# OBCv4_21.net
KiCad netlist of a schematic drawn in EAGLE
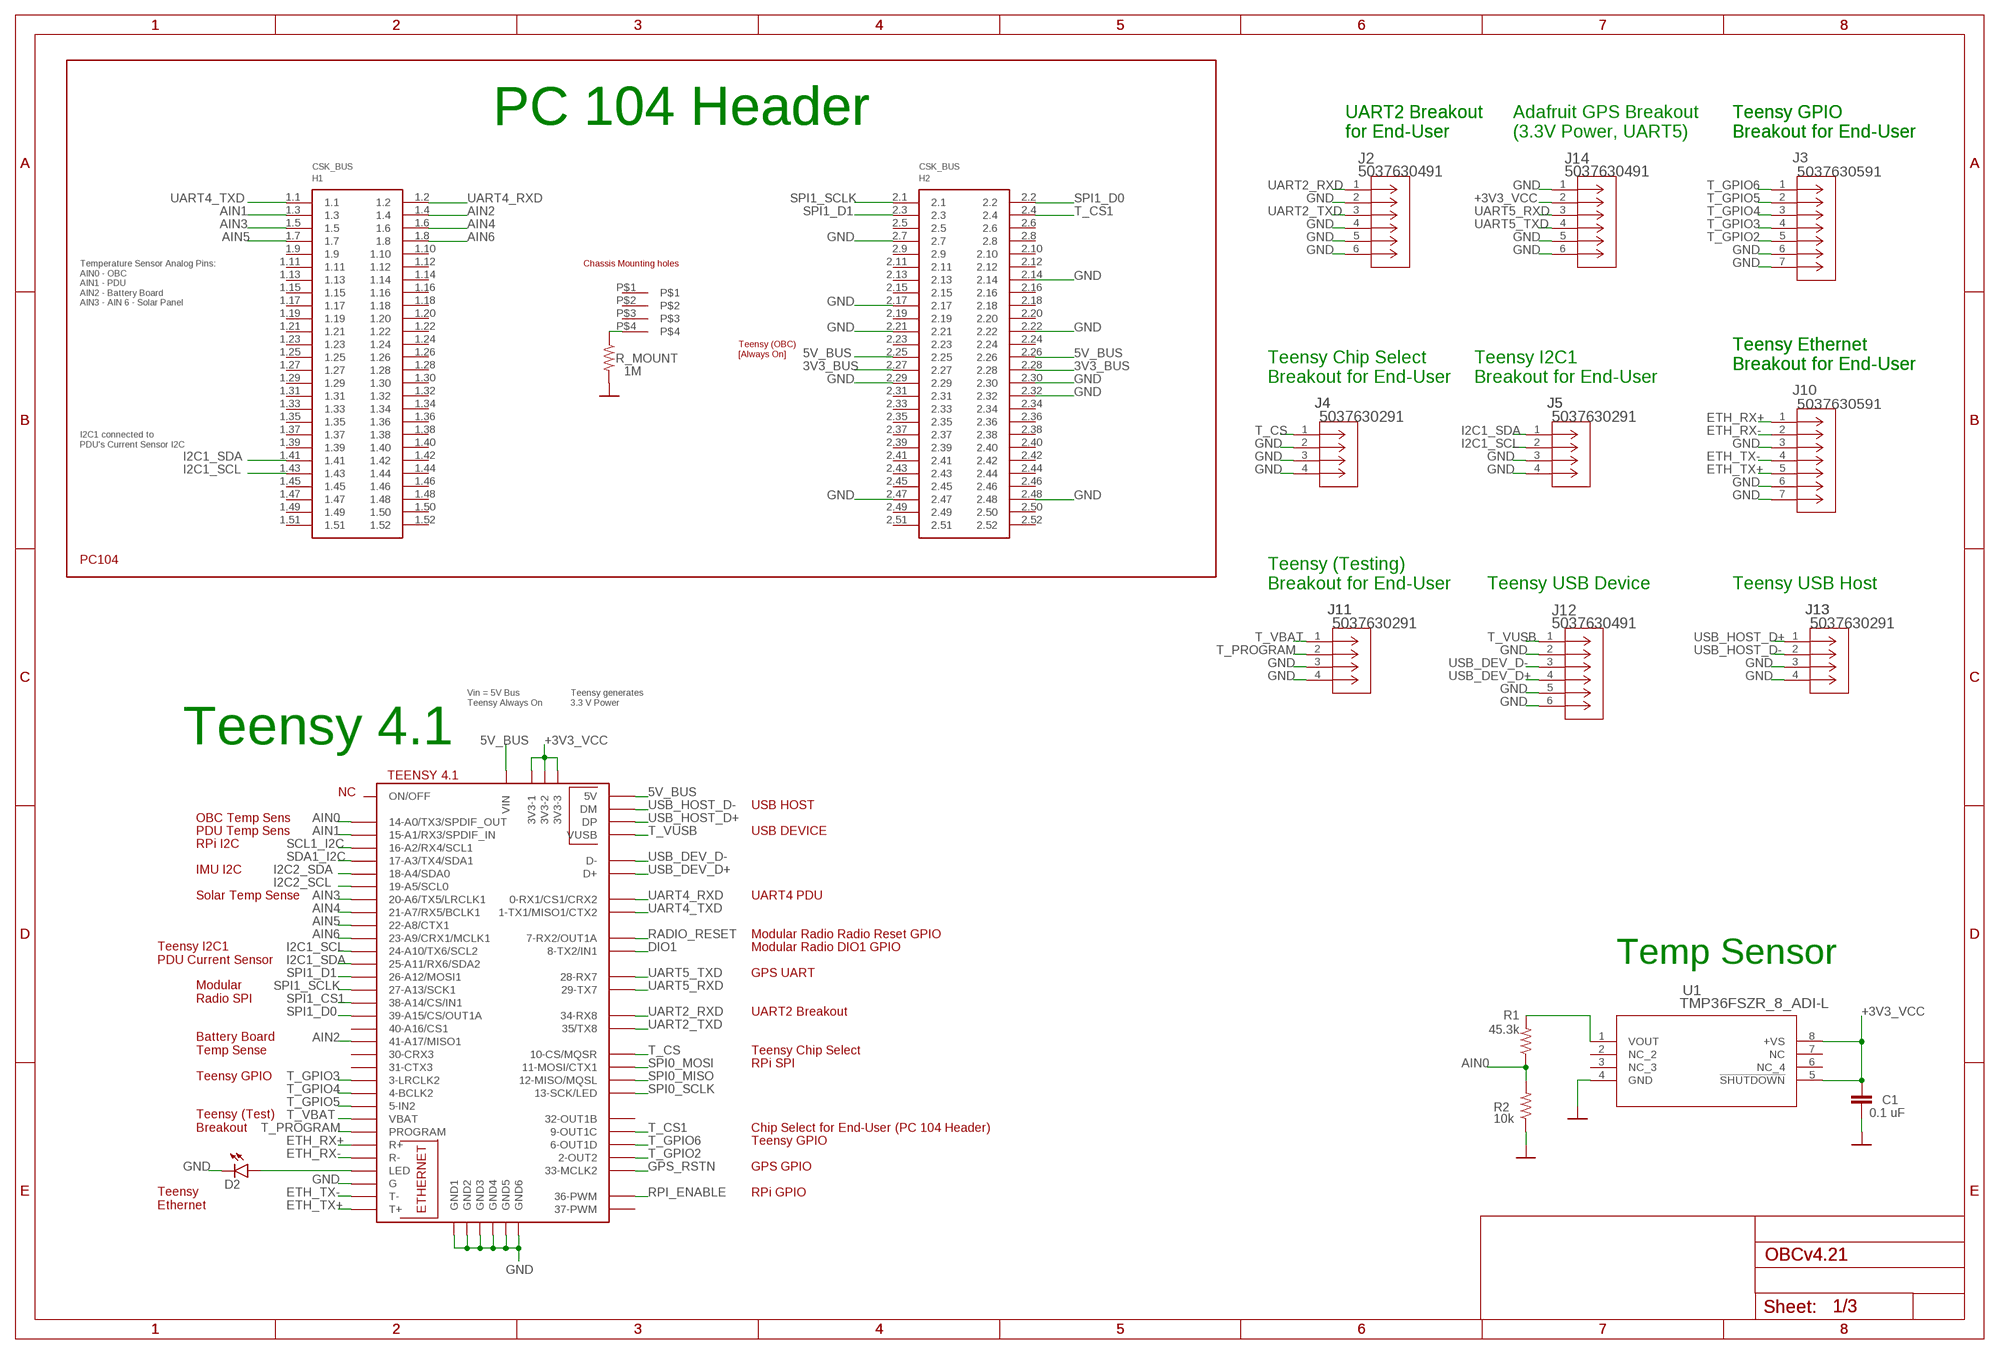
[diagram p0: schematic, sheet 1]
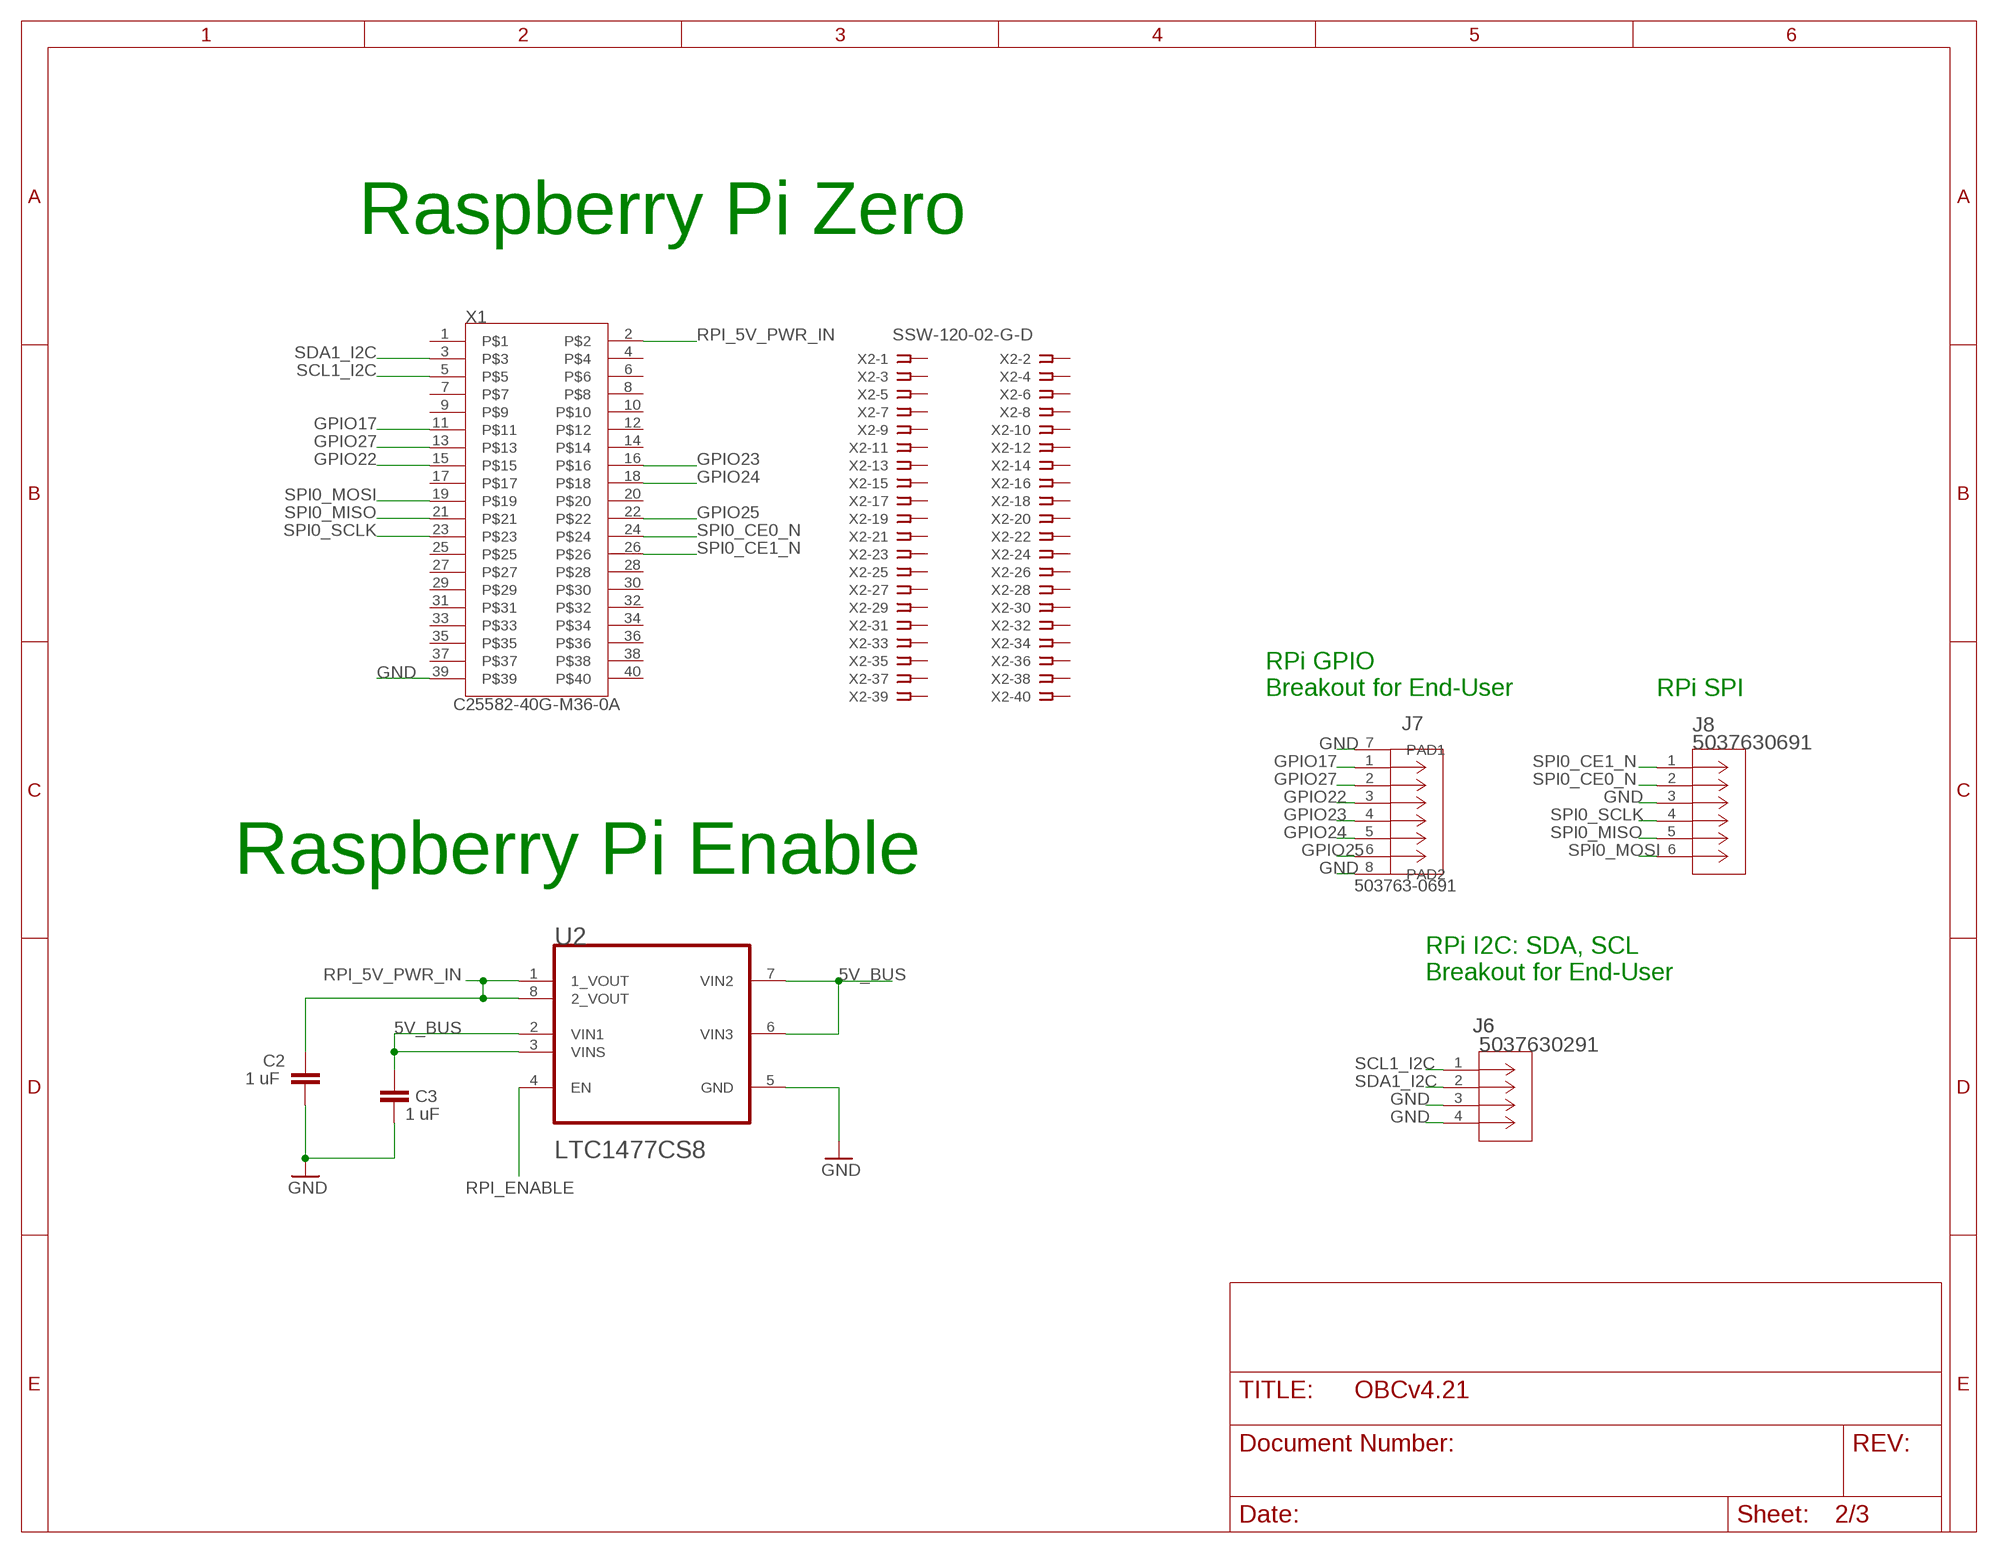
[diagram p1: schematic, sheet 2]
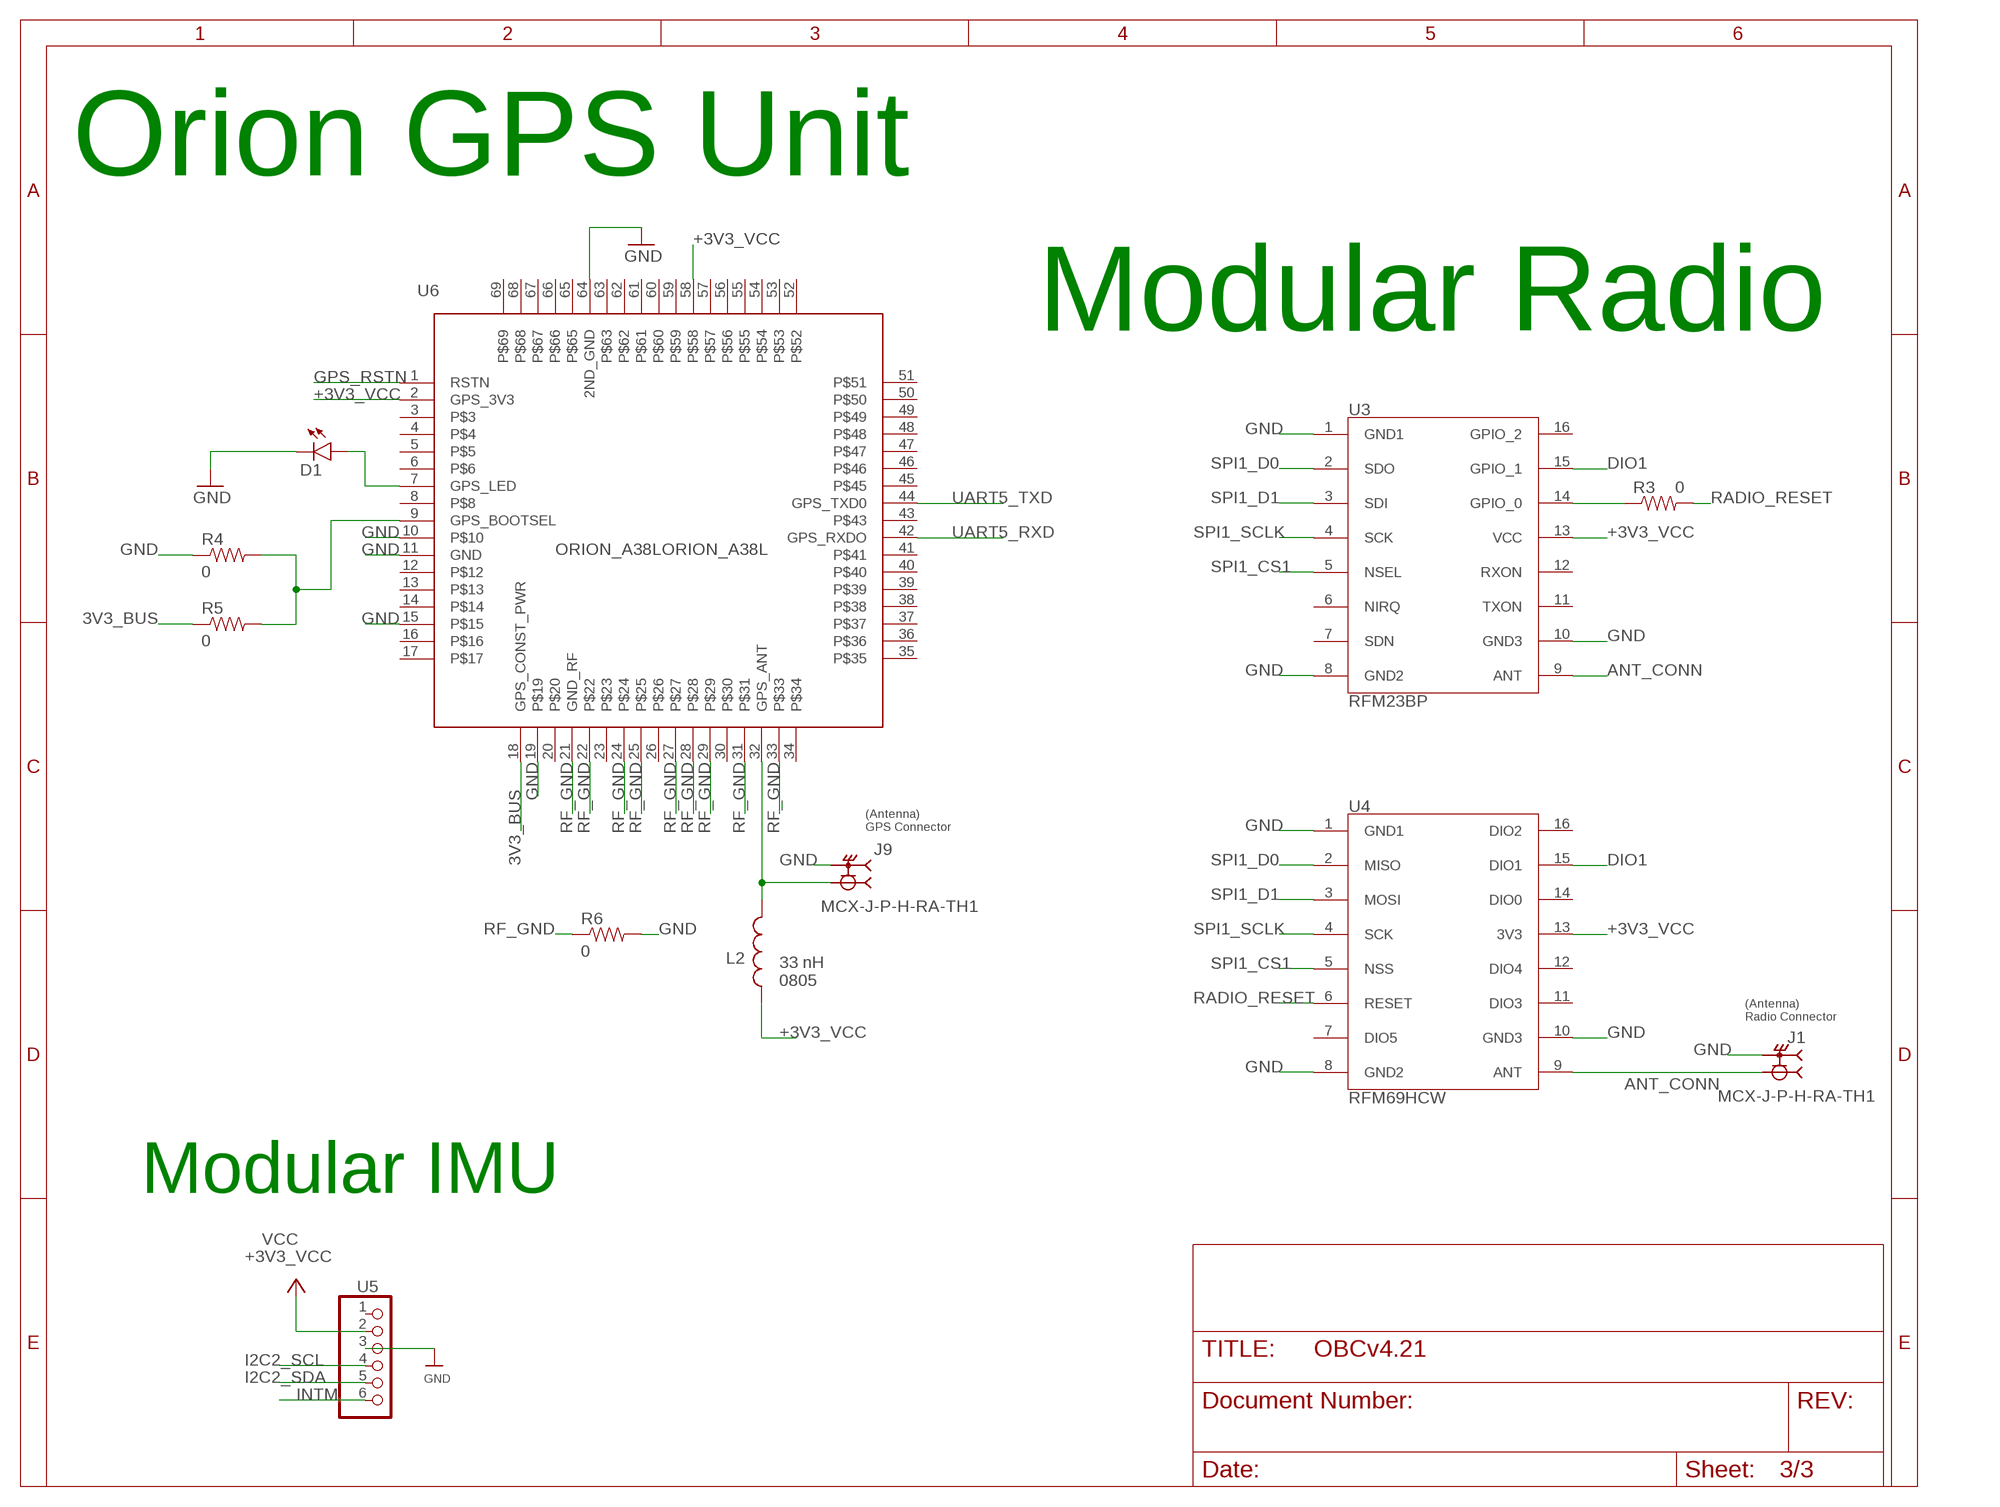
[diagram p2: schematic, sheet 3]

(export (version "E")
  (design (tool "Eeschema 10.0.6"))
  (components
    (comp (ref "D1")
      (value "LEDCHIP-LED0603")
      (footprint "eagle-import:CHIP-LED0603")
      (libsource (lib "eagle-import") (part "LEDCHIP-LED0603"))
    )
    (comp (ref "J1")
      (value "MCX-J-P-H-RA-TH1")
      (footprint "eagle-import:SAMTEC_MCX-J-P-H-RA-TH1")
      (fields (field (name "DIGI-KEY_PART_NUMBER") "SAM10607-ND") (field (name "MF") "Samtec"))
      (libsource (lib "eagle-import") (part "MCX-J-P-H-RA-TH1"))
    )
    (comp (ref "J9")
      (value "MCX-J-P-H-RA-TH1")
      (footprint "eagle-import:SAMTEC_MCX-J-P-H-RA-TH1")
      (fields (field (name "DIGI-KEY_PART_NUMBER") "SAM10607-ND") (field (name "MF") "Samtec"))
      (libsource (lib "eagle-import") (part "MCX-J-P-H-RA-TH1"))
    )
    (comp (ref "L2")
      (value "AIMC-0805-2N2S-T")
      (footprint "eagle-import:INDC2012X105N")
      (fields (field (name "DIGI-KEY_PART_NUMBER") "535-11562-1-ND") (field (name "MF") "Abracon"))
      (libsource (lib "eagle-import") (part "AIMC-0805-2N2S-T"))
    )
    (comp (ref "R3")
      (value "0")
      (footprint "eagle-import:0805")
      (libsource (lib "eagle-import") (part "RESISTOR0805-RES"))
    )
    (comp (ref "R4")
      (value "0")
      (footprint "eagle-import:0805")
      (libsource (lib "eagle-import") (part "RESISTOR0805-RES"))
    )
    (comp (ref "R5")
      (value "0")
      (footprint "eagle-import:0805")
      (libsource (lib "eagle-import") (part "RESISTOR0805-RES"))
    )
    (comp (ref "R6")
      (value "0")
      (footprint "eagle-import:0805")
      (libsource (lib "eagle-import") (part "RESISTOR0805-RES"))
    )
    (comp (ref "U3")
      (value "RFM23BP")
      (footprint "eagle-import:RFM23BP")
      (libsource (lib "eagle-import") (part "RFM23BP"))
    )
    (comp (ref "U4")
      (value "RFM69HCW")
      (footprint "eagle-import:RFM69HCW")
      (libsource (lib "eagle-import") (part "RFM69HCW"))
    )
    (comp (ref "U5")
      (value "HEADER-1X670MIL")
      (footprint "eagle-import:1X06_ROUND_70")
      (libsource (lib "eagle-import") (part "HEADER-1X670MIL"))
    )
    (comp (ref "U6")
      (value "ORION_A38LORION_A38L")
      (footprint "eagle-import:ORION_A38L")
      (libsource (lib "eagle-import") (part "ORION_A38LORION_A38L"))
    )
    (comp (ref "C1")
      (value "0.1 uF")
      (footprint "eagle-import:0805")
      (libsource (lib "eagle-import") (part "CAP0805"))
    )
    (comp (ref "D2")
      (value "LEDCHIP-LED0603")
      (footprint "eagle-import:CHIP-LED0603")
      (libsource (lib "eagle-import") (part "LEDCHIP-LED0603"))
    )
    (comp (ref "H1")
      (value "PC104_WCONN")
      (footprint "eagle-import:PC104_WCONN")
      (libsource (lib "eagle-import") (part "PC104_WCONN"))
    )
    (comp (ref "J2")
      (value "5037630491")
      (footprint "eagle-import:CON_5037630491")
      (fields (field (name "COPYRIGHT") "Copyright (C) 2018 Accelerated Designs. All rights reserved"))
      (libsource (lib "eagle-import") (part "5037630491"))
    )
    (comp (ref "J3")
      (value "5037630591")
      (footprint "eagle-import:CON_5037630591")
      (fields (field (name "COPYRIGHT") "Copyright (C) 2021 Ultra Librarian. All rights reserved."))
      (libsource (lib "eagle-import") (part "5037630591"))
    )
    (comp (ref "J4")
      (value "5037630291")
      (footprint "eagle-import:CON_5037630291")
      (fields (field (name "COPYRIGHT") "Copyright (C) 2018 Accelerated Designs. All rights reserved"))
      (libsource (lib "eagle-import") (part "5037630291"))
    )
    (comp (ref "J5")
      (value "5037630291")
      (footprint "eagle-import:CON_5037630291")
      (fields (field (name "COPYRIGHT") "Copyright (C) 2018 Accelerated Designs. All rights reserved"))
      (libsource (lib "eagle-import") (part "5037630291"))
    )
    (comp (ref "J10")
      (value "5037630591")
      (footprint "eagle-import:CON_5037630591")
      (fields (field (name "COPYRIGHT") "Copyright (C) 2021 Ultra Librarian. All rights reserved."))
      (libsource (lib "eagle-import") (part "5037630591"))
    )
    (comp (ref "J11")
      (value "5037630291")
      (footprint "eagle-import:CON_5037630291")
      (fields (field (name "COPYRIGHT") "Copyright (C) 2018 Accelerated Designs. All rights reserved"))
      (libsource (lib "eagle-import") (part "5037630291"))
    )
    (comp (ref "J12")
      (value "5037630491")
      (footprint "eagle-import:CON_5037630491")
      (fields (field (name "COPYRIGHT") "Copyright (C) 2018 Accelerated Designs. All rights reserved"))
      (libsource (lib "eagle-import") (part "5037630491"))
    )
    (comp (ref "J13")
      (value "5037630291")
      (footprint "eagle-import:CON_5037630291")
      (fields (field (name "COPYRIGHT") "Copyright (C) 2018 Accelerated Designs. All rights reserved"))
      (libsource (lib "eagle-import") (part "5037630291"))
    )
    (comp (ref "J14")
      (value "5037630491")
      (footprint "eagle-import:CON_5037630491")
      (fields (field (name "COPYRIGHT") "Copyright (C) 2018 Accelerated Designs. All rights reserved"))
      (libsource (lib "eagle-import") (part "5037630491"))
    )
    (comp (ref "R1")
      (value "45.3k")
      (footprint "eagle-import:0805")
      (libsource (lib "eagle-import") (part "RESISTOR0805-RES"))
    )
    (comp (ref "R2")
      (value "10k")
      (footprint "eagle-import:0805")
      (libsource (lib "eagle-import") (part "RESISTOR0805-RES"))
    )
    (comp (ref "R_MOUNT")
      (value "1M")
      (footprint "eagle-import:0805")
      (libsource (lib "eagle-import") (part "RESISTOR0805-RES"))
    )
    (comp (ref "U$1")
      (value "TEENSY41")
      (footprint "eagle-import:TEENSY41")
      (libsource (lib "eagle-import") (part "TEENSY41"))
    )
    (comp (ref "U1")
      (value "TMP36FSZR_8_ADI-L")
      (footprint "eagle-import:R_8_ADI-L")
      (fields
        (field (name "MANUFACTURER_PART_NUMBER") "TMP36FSZ")
        (field (name "COPYRIGHT") "Copyright (C) 2021 Ultra Librarian. All rights reserved.")
      )
      (libsource (lib "eagle-import") (part "TMP36FSZR_8_ADI-L"))
    )
    (comp (ref "C2")
      (value "1 uF")
      (footprint "eagle-import:0805")
      (libsource (lib "eagle-import") (part "CAP0805"))
    )
    (comp (ref "C3")
      (value "1 uF")
      (footprint "eagle-import:0805")
      (libsource (lib "eagle-import") (part "CAP0805"))
    )
    (comp (ref "J6")
      (value "5037630291")
      (footprint "eagle-import:CON_5037630291")
      (fields (field (name "COPYRIGHT") "Copyright (C) 2018 Accelerated Designs. All rights reserved"))
      (libsource (lib "eagle-import") (part "5037630291"))
    )
    (comp (ref "J7")
      (value "503763-0691")
      (footprint "eagle-import:CONN_503763-0691_MOL")
      (fields (field (name "COPYRIGHT") "Copyright (C) 2018 Accelerated Designs. All rights reserved"))
      (libsource (lib "eagle-import") (part "503763-0691"))
    )
    (comp (ref "J8")
      (value "5037630691")
      (footprint "eagle-import:CONN_503763-0691_MOL")
      (fields
        (field (name "MANUFACTURER_PART_NUMBER") "503763-0691")
        (field (name "COPYRIGHT") "Copyright (C) 2018 Accelerated Designs. All rights reserved")
      )
      (libsource (lib "eagle-import") (part "5037630691"))
    )
    (comp (ref "U2")
      (value "LTC1477CS8LINEAR_TECHNOLOGY_LTC1477CS8_0_2")
      (footprint "eagle-import:LINEAR_TECHNOLOGY_LTC1477CS8_2")
      (fields (field (name "MF") "Linear Technology") (field (name "MPN") "LTC1477CS8"))
      (libsource (lib "eagle-import") (part "LTC1477CS8LINEAR_TECHNOLOGY_LTC1477CS8_0_2"))
    )
    (comp (ref "X1")
      (value "C25582-40G-M36-0A")
      (footprint "eagle-import:ADAFRUIT_C25582-40G-M36-0A_0")
      (libsource (lib "eagle-import") (part "C25582-40G-M36-0A"))
    )
    (comp (ref "X2")
      (value "SSW-120-02-G-D")
      (footprint "eagle-import:SSW-120-02-G-D")
      (fields (field (name "MF") "Samtec Inc."))
      (libsource (lib "eagle-import") (part "SSW-120-02-G-D"))
    )
  )
  (nets
    (net (code "1") (name "+3V3_VCC") (class "Default")
      (node (ref "C1") (pin "1") (pinfunction "1_1") (pintype "passive"))
      (node (ref "J14") (pin "2") (pinfunction "2_2") (pintype "passive"))
      (node (ref "L2") (pin "1") (pinfunction "1_1") (pintype "passive"))
      (node (ref "U$1") (pin "3V3-1") (pinfunction "3V3-1_3V3-1") (pintype "bidirectional"))
      (node (ref "U$1") (pin "3V3-2") (pinfunction "3V3-2_3V3-2") (pintype "bidirectional"))
      (node (ref "U$1") (pin "3V3-3") (pinfunction "3V3-3_3V3-3") (pintype "bidirectional"))
      (node (ref "U1") (pin "5") (pinfunction "~{SHUTDOWN}_5") (pintype "passive"))
      (node (ref "U1") (pin "8") (pinfunction "+VS_8") (pintype "power_in"))
      (node (ref "U3") (pin "13") (pinfunction "VCC_13") (pintype "bidirectional"))
      (node (ref "U4") (pin "13") (pinfunction "3V3_13") (pintype "bidirectional"))
      (node (ref "U5") (pin "2") (pinfunction "2_2") (pintype "passive"))
      (node (ref "U6") (pin "2") (pinfunction "GPS_3V3_2") (pintype "bidirectional"))
      (node (ref "U6") (pin "58") (pinfunction "P$58_58") (pintype "bidirectional"))
    )
    (net (code "2") (name "3V3_BUS") (class "Default")
      (node (ref "H1") (pin "2.27") (pinfunction "2.27_2.27") (pintype "bidirectional"))
      (node (ref "H1") (pin "2.28") (pinfunction "2.28_2.28") (pintype "bidirectional"))
      (node (ref "R5") (pin "1") (pinfunction "1_1") (pintype "passive"))
      (node (ref "U6") (pin "18") (pinfunction "GPS_CONST_PWR_18") (pintype "bidirectional"))
    )
    (net (code "3") (name "5V_BUS") (class "Default")
      (node (ref "C3") (pin "1") (pinfunction "1_1") (pintype "passive"))
      (node (ref "H1") (pin "2.25") (pinfunction "2.25_2.25") (pintype "bidirectional"))
      (node (ref "H1") (pin "2.26") (pinfunction "2.26_2.26") (pintype "bidirectional"))
      (node (ref "U$1") (pin "+5V") (pinfunction "5V_+5V") (pintype "bidirectional"))
      (node (ref "U$1") (pin "VIN") (pinfunction "VIN_VIN") (pintype "bidirectional"))
      (node (ref "U2") (pin "2") (pinfunction "VIN1_2") (pintype "power_in"))
      (node (ref "U2") (pin "3") (pinfunction "VINS_3") (pintype "power_in"))
      (node (ref "U2") (pin "6") (pinfunction "VIN3_6") (pintype "power_in"))
      (node (ref "U2") (pin "7") (pinfunction "VIN2_7") (pintype "power_in"))
    )
    (net (code "4") (name "AIN0") (class "Default")
      (node (ref "R1") (pin "1") (pinfunction "1_1") (pintype "passive"))
      (node (ref "R2") (pin "2") (pinfunction "2_2") (pintype "passive"))
      (node (ref "U$1") (pin "14-A0/TX3/SPDIF_OUT") (pinfunction "14-A0/TX3/SPDIF_OUT_14-A0/TX3/SPDIF_OUT") (pintype "bidirectional"))
    )
    (net (code "5") (name "AIN1") (class "Default")
      (node (ref "H1") (pin "1.3") (pinfunction "1.3_1.3") (pintype "bidirectional"))
      (node (ref "U$1") (pin "15-A1/RX3/SPDIF_IN") (pinfunction "15-A1/RX3/SPDIF_IN_15-A1/RX3/SPDIF_IN") (pintype "bidirectional"))
    )
    (net (code "6") (name "AIN2") (class "Default")
      (node (ref "H1") (pin "1.4") (pinfunction "1.4_1.4") (pintype "bidirectional"))
      (node (ref "U$1") (pin "41-A17/MISO1") (pinfunction "41-A17/MISO1_41-A17/MISO1") (pintype "bidirectional"))
    )
    (net (code "7") (name "AIN3") (class "Default")
      (node (ref "H1") (pin "1.5") (pinfunction "1.5_1.5") (pintype "bidirectional"))
      (node (ref "U$1") (pin "20-A6/TX5/LRCLK1") (pinfunction "20-A6/TX5/LRCLK1_20-A6/TX5/LRCLK1") (pintype "bidirectional"))
    )
    (net (code "8") (name "AIN4") (class "Default")
      (node (ref "H1") (pin "1.6") (pinfunction "1.6_1.6") (pintype "bidirectional"))
      (node (ref "U$1") (pin "21-A7/RX5/BCLK1") (pinfunction "21-A7/RX5/BCLK1_21-A7/RX5/BCLK1") (pintype "bidirectional"))
    )
    (net (code "9") (name "AIN5") (class "Default")
      (node (ref "H1") (pin "1.7") (pinfunction "1.7_1.7") (pintype "bidirectional"))
      (node (ref "U$1") (pin "22-A8/CTX1") (pinfunction "22-A8/CTX1_22-A8/CTX1") (pintype "bidirectional"))
    )
    (net (code "10") (name "AIN6") (class "Default")
      (node (ref "H1") (pin "1.8") (pinfunction "1.8_1.8") (pintype "bidirectional"))
      (node (ref "U$1") (pin "23-A9/CRX1/MCLK1") (pinfunction "23-A9/CRX1/MCLK1_23-A9/CRX1/MCLK1") (pintype "bidirectional"))
    )
    (net (code "11") (name "ANT_CONN") (class "Default")
      (node (ref "J1") (pin "1") (pinfunction "1_1") (pintype "passive"))
      (node (ref "U3") (pin "9") (pinfunction "ANT_9") (pintype "bidirectional"))
      (node (ref "U4") (pin "9") (pinfunction "ANT_9") (pintype "bidirectional"))
    )
    (net (code "12") (name "DIO1") (class "Default")
      (node (ref "U$1") (pin "8-TX2/IN1") (pinfunction "8-TX2/IN1_8-TX2/IN1") (pintype "bidirectional"))
      (node (ref "U3") (pin "15") (pinfunction "GPIO_1_15") (pintype "bidirectional"))
      (node (ref "U4") (pin "15") (pinfunction "DIO1_15") (pintype "bidirectional"))
    )
    (net (code "13") (name "ETH_RX+") (class "Default")
      (node (ref "J10") (pin "1") (pinfunction "1_1") (pintype "passive"))
      (node (ref "U$1") (pin "R+") (pinfunction "R+_R+") (pintype "bidirectional"))
    )
    (net (code "14") (name "ETH_RX-") (class "Default")
      (node (ref "J10") (pin "2") (pinfunction "2_2") (pintype "passive"))
      (node (ref "U$1") (pin "R-") (pinfunction "R-_R-") (pintype "bidirectional"))
    )
    (net (code "15") (name "ETH_TX+") (class "Default")
      (node (ref "J10") (pin "5") (pinfunction "5_5") (pintype "passive"))
      (node (ref "U$1") (pin "T+") (pinfunction "T+_T+") (pintype "bidirectional"))
    )
    (net (code "16") (name "ETH_TX-") (class "Default")
      (node (ref "J10") (pin "4") (pinfunction "4_4") (pintype "passive"))
      (node (ref "U$1") (pin "T-") (pinfunction "T-_T-") (pintype "bidirectional"))
    )
    (net (code "17") (name "GND") (class "Default")
      (node (ref "C1") (pin "2") (pinfunction "2_2") (pintype "passive"))
      (node (ref "C2") (pin "2") (pinfunction "2_2") (pintype "passive"))
      (node (ref "C3") (pin "2") (pinfunction "2_2") (pintype "passive"))
      (node (ref "D1") (pin "C") (pinfunction "C_C") (pintype "passive"))
      (node (ref "D2") (pin "C") (pinfunction "C_C") (pintype "passive"))
      (node (ref "H1") (pin "2.14") (pinfunction "2.14_2.14") (pintype "bidirectional"))
      (node (ref "H1") (pin "2.17") (pinfunction "2.17_2.17") (pintype "bidirectional"))
      (node (ref "H1") (pin "2.21") (pinfunction "2.21_2.21") (pintype "bidirectional"))
      (node (ref "H1") (pin "2.22") (pinfunction "2.22_2.22") (pintype "bidirectional"))
      (node (ref "H1") (pin "2.29") (pinfunction "2.29_2.29") (pintype "bidirectional"))
      (node (ref "H1") (pin "2.30") (pinfunction "2.30_2.30") (pintype "bidirectional"))
      (node (ref "H1") (pin "2.32") (pinfunction "2.32_2.32") (pintype "bidirectional"))
      (node (ref "H1") (pin "2.47") (pinfunction "2.47_2.47") (pintype "bidirectional"))
      (node (ref "H1") (pin "2.48") (pinfunction "2.48_2.48") (pintype "bidirectional"))
      (node (ref "H1") (pin "2.7") (pinfunction "2.7_2.7") (pintype "bidirectional"))
      (node (ref "J1") (pin "S1") (pinfunction "2_S1") (pintype "passive"))
      (node (ref "J1") (pin "S2") (pinfunction "2_S2") (pintype "passive"))
      (node (ref "J1") (pin "S3") (pinfunction "2_S3") (pintype "passive"))
      (node (ref "J1") (pin "S4") (pinfunction "2_S4") (pintype "passive"))
      (node (ref "J10") (pin "3") (pinfunction "3_3") (pintype "passive"))
      (node (ref "J10") (pin "6") (pinfunction "6_6") (pintype "passive"))
      (node (ref "J10") (pin "7") (pinfunction "7_7") (pintype "passive"))
      (node (ref "J11") (pin "3") (pinfunction "3_3") (pintype "passive"))
      (node (ref "J11") (pin "4") (pinfunction "4_4") (pintype "passive"))
      (node (ref "J12") (pin "2") (pinfunction "2_2") (pintype "passive"))
      (node (ref "J12") (pin "5") (pinfunction "5_5") (pintype "passive"))
      (node (ref "J12") (pin "6") (pinfunction "6_6") (pintype "passive"))
      (node (ref "J13") (pin "3") (pinfunction "3_3") (pintype "passive"))
      (node (ref "J13") (pin "4") (pinfunction "4_4") (pintype "passive"))
      (node (ref "J14") (pin "1") (pinfunction "1_1") (pintype "passive"))
      (node (ref "J14") (pin "5") (pinfunction "5_5") (pintype "passive"))
      (node (ref "J14") (pin "6") (pinfunction "6_6") (pintype "passive"))
      (node (ref "J2") (pin "2") (pinfunction "2_2") (pintype "passive"))
      (node (ref "J2") (pin "4") (pinfunction "4_4") (pintype "passive"))
      (node (ref "J2") (pin "5") (pinfunction "5_5") (pintype "passive"))
      (node (ref "J2") (pin "6") (pinfunction "6_6") (pintype "passive"))
      (node (ref "J3") (pin "6") (pinfunction "6_6") (pintype "passive"))
      (node (ref "J3") (pin "7") (pinfunction "7_7") (pintype "passive"))
      (node (ref "J4") (pin "2") (pinfunction "2_2") (pintype "passive"))
      (node (ref "J4") (pin "3") (pinfunction "3_3") (pintype "passive"))
      (node (ref "J4") (pin "4") (pinfunction "4_4") (pintype "passive"))
      (node (ref "J5") (pin "3") (pinfunction "3_3") (pintype "passive"))
      (node (ref "J5") (pin "4") (pinfunction "4_4") (pintype "passive"))
      (node (ref "J6") (pin "3") (pinfunction "3_3") (pintype "passive"))
      (node (ref "J6") (pin "4") (pinfunction "4_4") (pintype "passive"))
      (node (ref "J7") (pin "7") (pinfunction "PAD1_7") (pintype "bidirectional"))
      (node (ref "J7") (pin "8") (pinfunction "PAD2_8") (pintype "bidirectional"))
      (node (ref "J8") (pin "3") (pinfunction "3_3") (pintype "passive"))
      (node (ref "J9") (pin "S1") (pinfunction "2_S1") (pintype "passive"))
      (node (ref "J9") (pin "S2") (pinfunction "2_S2") (pintype "passive"))
      (node (ref "J9") (pin "S3") (pinfunction "2_S3") (pintype "passive"))
      (node (ref "J9") (pin "S4") (pinfunction "2_S4") (pintype "passive"))
      (node (ref "R2") (pin "1") (pinfunction "1_1") (pintype "passive"))
      (node (ref "R4") (pin "1") (pinfunction "1_1") (pintype "passive"))
      (node (ref "R6") (pin "2") (pinfunction "2_2") (pintype "passive"))
      (node (ref "R_MOUNT") (pin "2") (pinfunction "2_2") (pintype "passive"))
      (node (ref "U$1") (pin "G") (pinfunction "G_G") (pintype "bidirectional"))
      (node (ref "U$1") (pin "GND1") (pinfunction "GND1_GND1") (pintype "bidirectional"))
      (node (ref "U$1") (pin "GND2") (pinfunction "GND2_GND2") (pintype "bidirectional"))
      (node (ref "U$1") (pin "GND3") (pinfunction "GND3_GND3") (pintype "bidirectional"))
      (node (ref "U$1") (pin "GND4") (pinfunction "GND4_GND4") (pintype "bidirectional"))
      (node (ref "U$1") (pin "GND5") (pinfunction "GND5_GND5") (pintype "bidirectional"))
      (node (ref "U$1") (pin "GND6") (pinfunction "GND6_GND6") (pintype "bidirectional"))
      (node (ref "U1") (pin "4") (pinfunction "GND_4") (pintype "passive"))
      (node (ref "U2") (pin "5") (pinfunction "GND_5") (pintype "power_in"))
      (node (ref "U3") (pin "1") (pinfunction "GND1_1") (pintype "bidirectional"))
      (node (ref "U3") (pin "10") (pinfunction "GND3_10") (pintype "bidirectional"))
      (node (ref "U3") (pin "8") (pinfunction "GND2_8") (pintype "bidirectional"))
      (node (ref "U4") (pin "1") (pinfunction "GND1_1") (pintype "bidirectional"))
      (node (ref "U4") (pin "10") (pinfunction "GND3_10") (pintype "bidirectional"))
      (node (ref "U4") (pin "8") (pinfunction "GND2_8") (pintype "bidirectional"))
      (node (ref "U5") (pin "3") (pinfunction "3_3") (pintype "passive"))
      (node (ref "U6") (pin "10") (pinfunction "P$10_10") (pintype "bidirectional"))
      (node (ref "U6") (pin "11") (pinfunction "GND_11") (pintype "bidirectional"))
      (node (ref "U6") (pin "15") (pinfunction "P$15_15") (pintype "bidirectional"))
      (node (ref "U6") (pin "19") (pinfunction "P$19_19") (pintype "bidirectional"))
      (node (ref "U6") (pin "64") (pinfunction "2ND_GND_64") (pintype "bidirectional"))
      (node (ref "X1") (pin "39") (pinfunction "P$39_39") (pintype "bidirectional"))
    )
    (net (code "18") (name "GPIO17") (class "Default")
      (node (ref "J7") (pin "1") (pinfunction "1_1") (pintype "passive"))
      (node (ref "X1") (pin "11") (pinfunction "P$11_11") (pintype "bidirectional"))
    )
    (net (code "19") (name "GPIO22") (class "Default")
      (node (ref "J7") (pin "3") (pinfunction "3_3") (pintype "passive"))
      (node (ref "X1") (pin "15") (pinfunction "P$15_15") (pintype "bidirectional"))
    )
    (net (code "20") (name "GPIO23") (class "Default")
      (node (ref "J7") (pin "4") (pinfunction "4_4") (pintype "passive"))
      (node (ref "X1") (pin "16") (pinfunction "P$16_16") (pintype "bidirectional"))
    )
    (net (code "21") (name "GPIO24") (class "Default")
      (node (ref "J7") (pin "5") (pinfunction "5_5") (pintype "passive"))
      (node (ref "X1") (pin "18") (pinfunction "P$18_18") (pintype "bidirectional"))
    )
    (net (code "22") (name "GPIO25") (class "Default")
      (node (ref "J7") (pin "6") (pinfunction "6_6") (pintype "passive"))
      (node (ref "X1") (pin "22") (pinfunction "P$22_22") (pintype "bidirectional"))
    )
    (net (code "23") (name "GPIO27") (class "Default")
      (node (ref "J7") (pin "2") (pinfunction "2_2") (pintype "passive"))
      (node (ref "X1") (pin "13") (pinfunction "P$13_13") (pintype "bidirectional"))
    )
    (net (code "24") (name "GPS_RSTN") (class "Default")
      (node (ref "U$1") (pin "33-MCLK2") (pinfunction "33-MCLK2_33-MCLK2") (pintype "bidirectional"))
      (node (ref "U6") (pin "1") (pinfunction "RSTN_1") (pintype "bidirectional"))
    )
    (net (code "25") (name "I2C1_SCL") (class "Default")
      (node (ref "H1") (pin "1.43") (pinfunction "1.43_1.43") (pintype "bidirectional"))
      (node (ref "J5") (pin "2") (pinfunction "2_2") (pintype "passive"))
      (node (ref "U$1") (pin "24-A10/TX6/SCL2") (pinfunction "24-A10/TX6/SCL2_24-A10/TX6/SCL2") (pintype "bidirectional"))
    )
    (net (code "26") (name "I2C1_SDA") (class "Default")
      (node (ref "H1") (pin "1.41") (pinfunction "1.41_1.41") (pintype "bidirectional"))
      (node (ref "J5") (pin "1") (pinfunction "1_1") (pintype "passive"))
      (node (ref "U$1") (pin "25-A11/RX6/SDA2") (pinfunction "25-A11/RX6/SDA2_25-A11/RX6/SDA2") (pintype "bidirectional"))
    )
    (net (code "27") (name "I2C2_SCL") (class "Default")
      (node (ref "U$1") (pin "19-A5/SCL0") (pinfunction "19-A5/SCL0_19-A5/SCL0") (pintype "bidirectional"))
      (node (ref "U5") (pin "4") (pinfunction "4_4") (pintype "passive"))
    )
    (net (code "28") (name "I2C2_SDA") (class "Default")
      (node (ref "U$1") (pin "18-A4/SDA0") (pinfunction "18-A4/SDA0_18-A4/SDA0") (pintype "bidirectional"))
      (node (ref "U5") (pin "5") (pinfunction "5_5") (pintype "passive"))
    )
    (net (code "29") (name "INTM") (class "Default")
      (node (ref "U5") (pin "6") (pinfunction "6_6") (pintype "passive"))
    )
    (net (code "30") (name "Net-(D2-PadA)") (class "Default")
      (node (ref "D2") (pin "A") (pinfunction "A_A") (pintype "passive"))
      (node (ref "U$1") (pin "LED") (pinfunction "LED_LED") (pintype "bidirectional"))
    )
    (net (code "31") (name "Net-(H1-PadP$4)") (class "Default")
      (node (ref "H1") (pin "P$4") (pinfunction "P$4_P$4") (pintype "bidirectional"))
      (node (ref "R_MOUNT") (pin "1") (pinfunction "1_1") (pintype "passive"))
    )
    (net (code "32") (name "Net-(U1-VOUT)") (class "Default")
      (node (ref "R1") (pin "2") (pinfunction "2_2") (pintype "passive"))
      (node (ref "U1") (pin "1") (pinfunction "VOUT_1") (pintype "output"))
    )
    (net (code "33") (name "Net-(U3-GPIO_0)") (class "Default")
      (node (ref "R3") (pin "1") (pinfunction "1_1") (pintype "passive"))
      (node (ref "U3") (pin "14") (pinfunction "GPIO_0_14") (pintype "bidirectional"))
    )
    (net (code "34") (name "Net-(U6-GPS_ANT)") (class "Default")
      (node (ref "J9") (pin "1") (pinfunction "1_1") (pintype "passive"))
      (node (ref "L2") (pin "2") (pinfunction "2_2") (pintype "passive"))
      (node (ref "U6") (pin "32") (pinfunction "GPS_ANT_32") (pintype "bidirectional"))
    )
    (net (code "35") (name "Net-(U6-GPS_BOOTSEL)") (class "Default")
      (node (ref "R4") (pin "2") (pinfunction "2_2") (pintype "passive"))
      (node (ref "R5") (pin "2") (pinfunction "2_2") (pintype "passive"))
      (node (ref "U6") (pin "9") (pinfunction "GPS_BOOTSEL_9") (pintype "bidirectional"))
    )
    (net (code "36") (name "Net-(U6-GPS_LED)") (class "Default")
      (node (ref "D1") (pin "A") (pinfunction "A_A") (pintype "passive"))
      (node (ref "U6") (pin "7") (pinfunction "GPS_LED_7") (pintype "bidirectional"))
    )
    (net (code "37") (name "RADIO_RESET") (class "Default")
      (node (ref "R3") (pin "2") (pinfunction "2_2") (pintype "passive"))
      (node (ref "U$1") (pin "7-RX2/OUT1A") (pinfunction "7-RX2/OUT1A_7-RX2/OUT1A") (pintype "bidirectional"))
      (node (ref "U4") (pin "6") (pinfunction "RESET_6") (pintype "bidirectional"))
    )
    (net (code "38") (name "RF_GND") (class "Default")
      (node (ref "R6") (pin "1") (pinfunction "1_1") (pintype "passive"))
      (node (ref "U6") (pin "21") (pinfunction "GND_RF_21") (pintype "bidirectional"))
      (node (ref "U6") (pin "22") (pinfunction "P$22_22") (pintype "bidirectional"))
      (node (ref "U6") (pin "24") (pinfunction "P$24_24") (pintype "bidirectional"))
      (node (ref "U6") (pin "25") (pinfunction "P$25_25") (pintype "bidirectional"))
      (node (ref "U6") (pin "27") (pinfunction "P$27_27") (pintype "bidirectional"))
      (node (ref "U6") (pin "28") (pinfunction "P$28_28") (pintype "bidirectional"))
      (node (ref "U6") (pin "29") (pinfunction "P$29_29") (pintype "bidirectional"))
      (node (ref "U6") (pin "31") (pinfunction "P$31_31") (pintype "bidirectional"))
      (node (ref "U6") (pin "33") (pinfunction "P$33_33") (pintype "bidirectional"))
    )
    (net (code "39") (name "RPI_5V_PWR_IN") (class "Default")
      (node (ref "C2") (pin "1") (pinfunction "1_1") (pintype "passive"))
      (node (ref "U2") (pin "1") (pinfunction "1_VOUT_1") (pintype "power_in"))
      (node (ref "U2") (pin "8") (pinfunction "2_VOUT_8") (pintype "power_in"))
      (node (ref "X1") (pin "2") (pinfunction "P$2_2") (pintype "bidirectional"))
    )
    (net (code "40") (name "RPI_ENABLE") (class "Default")
      (node (ref "U$1") (pin "36-PWM") (pinfunction "36-PWM_36-PWM") (pintype "bidirectional"))
      (node (ref "U2") (pin "4") (pinfunction "EN_4") (pintype "input"))
    )
    (net (code "41") (name "SCL1_I2C") (class "Default")
      (node (ref "J6") (pin "1") (pinfunction "1_1") (pintype "passive"))
      (node (ref "U$1") (pin "16-A2/RX4/SCL1") (pinfunction "16-A2/RX4/SCL1_16-A2/RX4/SCL1") (pintype "bidirectional"))
      (node (ref "X1") (pin "5") (pinfunction "P$5_5") (pintype "bidirectional"))
    )
    (net (code "42") (name "SDA1_I2C") (class "Default")
      (node (ref "J6") (pin "2") (pinfunction "2_2") (pintype "passive"))
      (node (ref "U$1") (pin "17-A3/TX4/SDA1") (pinfunction "17-A3/TX4/SDA1_17-A3/TX4/SDA1") (pintype "bidirectional"))
      (node (ref "X1") (pin "3") (pinfunction "P$3_3") (pintype "bidirectional"))
    )
    (net (code "43") (name "SPI0_CE0_N") (class "Default")
      (node (ref "J8") (pin "2") (pinfunction "2_2") (pintype "passive"))
      (node (ref "X1") (pin "24") (pinfunction "P$24_24") (pintype "bidirectional"))
    )
    (net (code "44") (name "SPI0_CE1_N") (class "Default")
      (node (ref "J8") (pin "1") (pinfunction "1_1") (pintype "passive"))
      (node (ref "X1") (pin "26") (pinfunction "P$26_26") (pintype "bidirectional"))
    )
    (net (code "45") (name "SPI0_MISO") (class "Default")
      (node (ref "J8") (pin "5") (pinfunction "5_5") (pintype "passive"))
      (node (ref "U$1") (pin "12-MISO/MQSL") (pinfunction "12-MISO/MQSL_12-MISO/MQSL") (pintype "bidirectional"))
      (node (ref "X1") (pin "21") (pinfunction "P$21_21") (pintype "bidirectional"))
    )
    (net (code "46") (name "SPI0_MOSI") (class "Default")
      (node (ref "J8") (pin "6") (pinfunction "6_6") (pintype "passive"))
      (node (ref "U$1") (pin "11-MOSI/CTX1") (pinfunction "11-MOSI/CTX1_11-MOSI/CTX1") (pintype "bidirectional"))
      (node (ref "X1") (pin "19") (pinfunction "P$19_19") (pintype "bidirectional"))
    )
    (net (code "47") (name "SPI0_SCLK") (class "Default")
      (node (ref "J8") (pin "4") (pinfunction "4_4") (pintype "passive"))
      (node (ref "U$1") (pin "13-SCK/LED") (pinfunction "13-SCK/LED_13-SCK/LED") (pintype "bidirectional"))
      (node (ref "X1") (pin "23") (pinfunction "P$23_23") (pintype "bidirectional"))
    )
    (net (code "48") (name "SPI1_CS1") (class "Default")
      (node (ref "U$1") (pin "38-A14/CS/IN1") (pinfunction "38-A14/CS/IN1_38-A14/CS/IN1") (pintype "bidirectional"))
      (node (ref "U3") (pin "5") (pinfunction "NSEL_5") (pintype "bidirectional"))
      (node (ref "U4") (pin "5") (pinfunction "NSS_5") (pintype "bidirectional"))
    )
    (net (code "49") (name "SPI1_D0") (class "Default")
      (node (ref "H1") (pin "2.2") (pinfunction "2.2_2.2") (pintype "bidirectional"))
      (node (ref "U$1") (pin "39-A15/CS/OUT1A") (pinfunction "39-A15/CS/OUT1A_39-A15/CS/OUT1A") (pintype "bidirectional"))
      (node (ref "U3") (pin "2") (pinfunction "SDO_2") (pintype "bidirectional"))
      (node (ref "U4") (pin "2") (pinfunction "MISO_2") (pintype "bidirectional"))
    )
    (net (code "50") (name "SPI1_D1") (class "Default")
      (node (ref "H1") (pin "2.3") (pinfunction "2.3_2.3") (pintype "bidirectional"))
      (node (ref "U$1") (pin "26-A12/MOSI1") (pinfunction "26-A12/MOSI1_26-A12/MOSI1") (pintype "bidirectional"))
      (node (ref "U3") (pin "3") (pinfunction "SDI_3") (pintype "bidirectional"))
      (node (ref "U4") (pin "3") (pinfunction "MOSI_3") (pintype "bidirectional"))
    )
    (net (code "51") (name "SPI1_SCLK") (class "Default")
      (node (ref "H1") (pin "2.1") (pinfunction "2.1_2.1") (pintype "bidirectional"))
      (node (ref "U$1") (pin "27-A13/SCK1") (pinfunction "27-A13/SCK1_27-A13/SCK1") (pintype "bidirectional"))
      (node (ref "U3") (pin "4") (pinfunction "SCK_4") (pintype "bidirectional"))
      (node (ref "U4") (pin "4") (pinfunction "SCK_4") (pintype "bidirectional"))
    )
    (net (code "52") (name "T_CS") (class "Default")
      (node (ref "J4") (pin "1") (pinfunction "1_1") (pintype "passive"))
      (node (ref "U$1") (pin "10-CS\\MQSR") (pinfunction "10-CS/MQSR_10-CS\\MQSR") (pintype "bidirectional"))
    )
    (net (code "53") (name "T_CS1") (class "Default")
      (node (ref "H1") (pin "2.4") (pinfunction "2.4_2.4") (pintype "bidirectional"))
      (node (ref "U$1") (pin "9-OUT1C") (pinfunction "9-OUT1C_9-OUT1C") (pintype "bidirectional"))
    )
    (net (code "54") (name "T_GPIO2") (class "Default")
      (node (ref "J3") (pin "5") (pinfunction "5_5") (pintype "passive"))
      (node (ref "U$1") (pin "2-OUT2") (pinfunction "2-OUT2_2-OUT2") (pintype "bidirectional"))
    )
    (net (code "55") (name "T_GPIO3") (class "Default")
      (node (ref "J3") (pin "4") (pinfunction "4_4") (pintype "passive"))
      (node (ref "U$1") (pin "3-LRCLK2") (pinfunction "3-LRCLK2_3-LRCLK2") (pintype "bidirectional"))
    )
    (net (code "56") (name "T_GPIO4") (class "Default")
      (node (ref "J3") (pin "3") (pinfunction "3_3") (pintype "passive"))
      (node (ref "U$1") (pin "4-BCLK2") (pinfunction "4-BCLK2_4-BCLK2") (pintype "bidirectional"))
    )
    (net (code "57") (name "T_GPIO5") (class "Default")
      (node (ref "J3") (pin "2") (pinfunction "2_2") (pintype "passive"))
      (node (ref "U$1") (pin "5-IN2") (pinfunction "5-IN2_5-IN2") (pintype "bidirectional"))
    )
    (net (code "58") (name "T_GPIO6") (class "Default")
      (node (ref "J3") (pin "1") (pinfunction "1_1") (pintype "passive"))
      (node (ref "U$1") (pin "6-OUT1D") (pinfunction "6-OUT1D_6-OUT1D") (pintype "bidirectional"))
    )
    (net (code "59") (name "T_PROGRAM") (class "Default")
      (node (ref "J11") (pin "2") (pinfunction "2_2") (pintype "passive"))
      (node (ref "U$1") (pin "PROGRAM") (pinfunction "PROGRAM_PROGRAM") (pintype "bidirectional"))
    )
    (net (code "60") (name "T_VBAT") (class "Default")
      (node (ref "J11") (pin "1") (pinfunction "1_1") (pintype "passive"))
      (node (ref "U$1") (pin "VBAT") (pinfunction "VBAT_VBAT") (pintype "bidirectional"))
    )
    (net (code "61") (name "T_VUSB") (class "Default")
      (node (ref "J12") (pin "1") (pinfunction "1_1") (pintype "passive"))
      (node (ref "U$1") (pin "VUSB") (pinfunction "VUSB_VUSB") (pintype "bidirectional"))
    )
    (net (code "62") (name "UART2_RXD") (class "Default")
      (node (ref "J2") (pin "1") (pinfunction "1_1") (pintype "passive"))
      (node (ref "U$1") (pin "34-RX8") (pinfunction "34-RX8_34-RX8") (pintype "bidirectional"))
    )
    (net (code "63") (name "UART2_TXD") (class "Default")
      (node (ref "J2") (pin "3") (pinfunction "3_3") (pintype "passive"))
      (node (ref "U$1") (pin "35-TX8") (pinfunction "35/TX8_35-TX8") (pintype "bidirectional"))
    )
    (net (code "64") (name "UART4_RXD") (class "Default")
      (node (ref "H1") (pin "1.2") (pinfunction "1.2_1.2") (pintype "bidirectional"))
      (node (ref "U$1") (pin "0-RX1/CS1/CRX2") (pinfunction "0-RX1/CS1/CRX2_0-RX1/CS1/CRX2") (pintype "bidirectional"))
    )
    (net (code "65") (name "UART4_TXD") (class "Default")
      (node (ref "H1") (pin "1.1") (pinfunction "1.1_1.1") (pintype "bidirectional"))
      (node (ref "U$1") (pin "1-TX1/MISO1/CTX2") (pinfunction "1-TX1/MISO1/CTX2_1-TX1/MISO1/CTX2") (pintype "bidirectional"))
    )
    (net (code "66") (name "UART5_RXD") (class "Default")
      (node (ref "J14") (pin "3") (pinfunction "3_3") (pintype "passive"))
      (node (ref "U$1") (pin "29-TX7") (pinfunction "29-TX7_29-TX7") (pintype "bidirectional"))
      (node (ref "U6") (pin "42") (pinfunction "GPS_RXDO_42") (pintype "input"))
    )
    (net (code "67") (name "UART5_TXD") (class "Default")
      (node (ref "J14") (pin "4") (pinfunction "4_4") (pintype "passive"))
      (node (ref "U$1") (pin "28-RX7") (pinfunction "28-RX7_28-RX7") (pintype "bidirectional"))
      (node (ref "U6") (pin "44") (pinfunction "GPS_TXD0_44") (pintype "output"))
    )
    (net (code "68") (name "USB_DEV_D+") (class "Default")
      (node (ref "J12") (pin "4") (pinfunction "4_4") (pintype "passive"))
      (node (ref "U$1") (pin "D+") (pinfunction "D+_D+") (pintype "bidirectional"))
    )
    (net (code "69") (name "USB_DEV_D-") (class "Default")
      (node (ref "J12") (pin "3") (pinfunction "3_3") (pintype "passive"))
      (node (ref "U$1") (pin "D-") (pinfunction "D-_D-") (pintype "bidirectional"))
    )
    (net (code "70") (name "USB_HOST_D+") (class "Default")
      (node (ref "J13") (pin "1") (pinfunction "1_1") (pintype "passive"))
      (node (ref "U$1") (pin "DP") (pinfunction "DP_DP") (pintype "bidirectional"))
    )
    (net (code "71") (name "USB_HOST_D-") (class "Default")
      (node (ref "J13") (pin "2") (pinfunction "2_2") (pintype "passive"))
      (node (ref "U$1") (pin "DM") (pinfunction "DM_DM") (pintype "bidirectional"))
    )
    (net (code "72") (name "unconnected-(H1-Pad1.9)") (class "Default")
      (node (ref "H1") (pin "1.9") (pinfunction "1.9_1.9") (pintype "bidirectional"))
    )
    (net (code "73") (name "unconnected-(H1-Pad1.10)") (class "Default")
      (node (ref "H1") (pin "1.10") (pinfunction "1.10_1.10") (pintype "bidirectional"))
    )
    (net (code "74") (name "unconnected-(H1-Pad1.11)") (class "Default")
      (node (ref "H1") (pin "1.11") (pinfunction "1.11_1.11") (pintype "bidirectional"))
    )
    (net (code "75") (name "unconnected-(H1-Pad1.12)") (class "Default")
      (node (ref "H1") (pin "1.12") (pinfunction "1.12_1.12") (pintype "bidirectional"))
    )
    (net (code "76") (name "unconnected-(H1-Pad1.13)") (class "Default")
      (node (ref "H1") (pin "1.13") (pinfunction "1.13_1.13") (pintype "bidirectional"))
    )
    (net (code "77") (name "unconnected-(H1-Pad1.14)") (class "Default")
      (node (ref "H1") (pin "1.14") (pinfunction "1.14_1.14") (pintype "bidirectional"))
    )
    (net (code "78") (name "unconnected-(H1-Pad1.15)") (class "Default")
      (node (ref "H1") (pin "1.15") (pinfunction "1.15_1.15") (pintype "bidirectional"))
    )
    (net (code "79") (name "unconnected-(H1-Pad1.16)") (class "Default")
      (node (ref "H1") (pin "1.16") (pinfunction "1.16_1.16") (pintype "bidirectional"))
    )
    (net (code "80") (name "unconnected-(H1-Pad1.17)") (class "Default")
      (node (ref "H1") (pin "1.17") (pinfunction "1.17_1.17") (pintype "bidirectional"))
    )
    (net (code "81") (name "unconnected-(H1-Pad1.18)") (class "Default")
      (node (ref "H1") (pin "1.18") (pinfunction "1.18_1.18") (pintype "bidirectional"))
    )
    (net (code "82") (name "unconnected-(H1-Pad1.19)") (class "Default")
      (node (ref "H1") (pin "1.19") (pinfunction "1.19_1.19") (pintype "bidirectional"))
    )
    (net (code "83") (name "unconnected-(H1-Pad1.20)") (class "Default")
      (node (ref "H1") (pin "1.20") (pinfunction "1.20_1.20") (pintype "bidirectional"))
    )
    (net (code "84") (name "unconnected-(H1-Pad1.21)") (class "Default")
      (node (ref "H1") (pin "1.21") (pinfunction "1.21_1.21") (pintype "bidirectional"))
    )
    (net (code "85") (name "unconnected-(H1-Pad1.22)") (class "Default")
      (node (ref "H1") (pin "1.22") (pinfunction "1.22_1.22") (pintype "bidirectional"))
    )
    (net (code "86") (name "unconnected-(H1-Pad1.23)") (class "Default")
      (node (ref "H1") (pin "1.23") (pinfunction "1.23_1.23") (pintype "bidirectional"))
    )
    (net (code "87") (name "unconnected-(H1-Pad1.24)") (class "Default")
      (node (ref "H1") (pin "1.24") (pinfunction "1.24_1.24") (pintype "bidirectional"))
    )
    (net (code "88") (name "unconnected-(H1-Pad1.25)") (class "Default")
      (node (ref "H1") (pin "1.25") (pinfunction "1.25_1.25") (pintype "bidirectional"))
    )
    (net (code "89") (name "unconnected-(H1-Pad1.26)") (class "Default")
      (node (ref "H1") (pin "1.26") (pinfunction "1.26_1.26") (pintype "bidirectional"))
    )
    (net (code "90") (name "unconnected-(H1-Pad1.27)") (class "Default")
      (node (ref "H1") (pin "1.27") (pinfunction "1.27_1.27") (pintype "bidirectional"))
    )
    (net (code "91") (name "unconnected-(H1-Pad1.28)") (class "Default")
      (node (ref "H1") (pin "1.28") (pinfunction "1.28_1.28") (pintype "bidirectional"))
    )
    (net (code "92") (name "unconnected-(H1-Pad1.29)") (class "Default")
      (node (ref "H1") (pin "1.29") (pinfunction "1.29_1.29") (pintype "bidirectional"))
    )
    (net (code "93") (name "unconnected-(H1-Pad1.30)") (class "Default")
      (node (ref "H1") (pin "1.30") (pinfunction "1.30_1.30") (pintype "bidirectional"))
    )
    (net (code "94") (name "unconnected-(H1-Pad1.31)") (class "Default")
      (node (ref "H1") (pin "1.31") (pinfunction "1.31_1.31") (pintype "bidirectional"))
    )
    (net (code "95") (name "unconnected-(H1-Pad1.32)") (class "Default")
      (node (ref "H1") (pin "1.32") (pinfunction "1.32_1.32") (pintype "bidirectional"))
    )
    (net (code "96") (name "unconnected-(H1-Pad1.33)") (class "Default")
      (node (ref "H1") (pin "1.33") (pinfunction "1.33_1.33") (pintype "bidirectional"))
    )
    (net (code "97") (name "unconnected-(H1-Pad1.34)") (class "Default")
      (node (ref "H1") (pin "1.34") (pinfunction "1.34_1.34") (pintype "bidirectional"))
    )
    (net (code "98") (name "unconnected-(H1-Pad1.35)") (class "Default")
      (node (ref "H1") (pin "1.35") (pinfunction "1.35_1.35") (pintype "bidirectional"))
    )
    (net (code "99") (name "unconnected-(H1-Pad1.36)") (class "Default")
      (node (ref "H1") (pin "1.36") (pinfunction "1.36_1.36") (pintype "bidirectional"))
    )
    (net (code "100") (name "unconnected-(H1-Pad1.37)") (class "Default")
      (node (ref "H1") (pin "1.37") (pinfunction "1.37_1.37") (pintype "bidirectional"))
    )
    (net (code "101") (name "unconnected-(H1-Pad1.38)") (class "Default")
      (node (ref "H1") (pin "1.38") (pinfunction "1.38_1.38") (pintype "bidirectional"))
    )
    (net (code "102") (name "unconnected-(H1-Pad1.39)") (class "Default")
      (node (ref "H1") (pin "1.39") (pinfunction "1.39_1.39") (pintype "bidirectional"))
    )
    (net (code "103") (name "unconnected-(H1-Pad1.40)") (class "Default")
      (node (ref "H1") (pin "1.40") (pinfunction "1.40_1.40") (pintype "bidirectional"))
    )
    (net (code "104") (name "unconnected-(H1-Pad1.42)") (class "Default")
      (node (ref "H1") (pin "1.42") (pinfunction "1.42_1.42") (pintype "bidirectional"))
    )
    (net (code "105") (name "unconnected-(H1-Pad1.44)") (class "Default")
      (node (ref "H1") (pin "1.44") (pinfunction "1.44_1.44") (pintype "bidirectional"))
    )
    (net (code "106") (name "unconnected-(H1-Pad1.45)") (class "Default")
      (node (ref "H1") (pin "1.45") (pinfunction "1.45_1.45") (pintype "bidirectional"))
    )
    (net (code "107") (name "unconnected-(H1-Pad1.46)") (class "Default")
      (node (ref "H1") (pin "1.46") (pinfunction "1.46_1.46") (pintype "bidirectional"))
    )
    (net (code "108") (name "unconnected-(H1-Pad1.47)") (class "Default")
      (node (ref "H1") (pin "1.47") (pinfunction "1.47_1.47") (pintype "bidirectional"))
    )
    (net (code "109") (name "unconnected-(H1-Pad1.48)") (class "Default")
      (node (ref "H1") (pin "1.48") (pinfunction "1.48_1.48") (pintype "bidirectional"))
    )
    (net (code "110") (name "unconnected-(H1-Pad1.49)") (class "Default")
      (node (ref "H1") (pin "1.49") (pinfunction "1.49_1.49") (pintype "bidirectional"))
    )
    (net (code "111") (name "unconnected-(H1-Pad1.50)") (class "Default")
      (node (ref "H1") (pin "1.50") (pinfunction "1.50_1.50") (pintype "bidirectional"))
    )
    (net (code "112") (name "unconnected-(H1-Pad1.51)") (class "Default")
      (node (ref "H1") (pin "1.51") (pinfunction "1.51_1.51") (pintype "bidirectional"))
    )
    (net (code "113") (name "unconnected-(H1-Pad1.52)") (class "Default")
      (node (ref "H1") (pin "1.52") (pinfunction "1.52_1.52") (pintype "bidirectional"))
    )
    (net (code "114") (name "unconnected-(H1-Pad2.5)") (class "Default")
      (node (ref "H1") (pin "2.5") (pinfunction "2.5_2.5") (pintype "bidirectional"))
    )
    (net (code "115") (name "unconnected-(H1-Pad2.6)") (class "Default")
      (node (ref "H1") (pin "2.6") (pinfunction "2.6_2.6") (pintype "bidirectional"))
    )
    (net (code "116") (name "unconnected-(H1-Pad2.8)") (class "Default")
      (node (ref "H1") (pin "2.8") (pinfunction "2.8_2.8") (pintype "bidirectional"))
    )
    (net (code "117") (name "unconnected-(H1-Pad2.9)") (class "Default")
      (node (ref "H1") (pin "2.9") (pinfunction "2.9_2.9") (pintype "bidirectional"))
    )
    (net (code "118") (name "unconnected-(H1-Pad2.10)") (class "Default")
      (node (ref "H1") (pin "2.10") (pinfunction "2.10_2.10") (pintype "bidirectional"))
    )
    (net (code "119") (name "unconnected-(H1-Pad2.11)") (class "Default")
      (node (ref "H1") (pin "2.11") (pinfunction "2.11_2.11") (pintype "bidirectional"))
    )
    (net (code "120") (name "unconnected-(H1-Pad2.12)") (class "Default")
      (node (ref "H1") (pin "2.12") (pinfunction "2.12_2.12") (pintype "bidirectional"))
    )
    (net (code "121") (name "unconnected-(H1-Pad2.13)") (class "Default")
      (node (ref "H1") (pin "2.13") (pinfunction "2.13_2.13") (pintype "bidirectional"))
    )
    (net (code "122") (name "unconnected-(H1-Pad2.15)") (class "Default")
      (node (ref "H1") (pin "2.15") (pinfunction "2.15_2.15") (pintype "bidirectional"))
    )
    (net (code "123") (name "unconnected-(H1-Pad2.16)") (class "Default")
      (node (ref "H1") (pin "2.16") (pinfunction "2.16_2.16") (pintype "bidirectional"))
    )
    (net (code "124") (name "unconnected-(H1-Pad2.18)") (class "Default")
      (node (ref "H1") (pin "2.18") (pinfunction "2.18_2.18") (pintype "bidirectional"))
    )
    (net (code "125") (name "unconnected-(H1-Pad2.19)") (class "Default")
      (node (ref "H1") (pin "2.19") (pinfunction "2.19_2.19") (pintype "bidirectional"))
    )
    (net (code "126") (name "unconnected-(H1-Pad2.20)") (class "Default")
      (node (ref "H1") (pin "2.20") (pinfunction "2.20_2.20") (pintype "bidirectional"))
    )
    (net (code "127") (name "unconnected-(H1-Pad2.23)") (class "Default")
      (node (ref "H1") (pin "2.23") (pinfunction "2.23_2.23") (pintype "bidirectional"))
    )
    (net (code "128") (name "unconnected-(H1-Pad2.24)") (class "Default")
      (node (ref "H1") (pin "2.24") (pinfunction "2.24_2.24") (pintype "bidirectional"))
    )
    (net (code "129") (name "unconnected-(H1-Pad2.31)") (class "Default")
      (node (ref "H1") (pin "2.31") (pinfunction "2.31_2.31") (pintype "bidirectional"))
    )
    (net (code "130") (name "unconnected-(H1-Pad2.33)") (class "Default")
      (node (ref "H1") (pin "2.33") (pinfunction "2.33_2.33") (pintype "bidirectional"))
    )
    (net (code "131") (name "unconnected-(H1-Pad2.34)") (class "Default")
      (node (ref "H1") (pin "2.34") (pinfunction "2.34_2.34") (pintype "bidirectional"))
    )
    (net (code "132") (name "unconnected-(H1-Pad2.35)") (class "Default")
      (node (ref "H1") (pin "2.35") (pinfunction "2.35_2.35") (pintype "bidirectional"))
    )
    (net (code "133") (name "unconnected-(H1-Pad2.36)") (class "Default")
      (node (ref "H1") (pin "2.36") (pinfunction "2.36_2.36") (pintype "bidirectional"))
    )
    (net (code "134") (name "unconnected-(H1-Pad2.37)") (class "Default")
      (node (ref "H1") (pin "2.37") (pinfunction "2.37_2.37") (pintype "bidirectional"))
    )
    (net (code "135") (name "unconnected-(H1-Pad2.38)") (class "Default")
      (node (ref "H1") (pin "2.38") (pinfunction "2.38_2.38") (pintype "bidirectional"))
    )
    (net (code "136") (name "unconnected-(H1-Pad2.39)") (class "Default")
      (node (ref "H1") (pin "2.39") (pinfunction "2.39_2.39") (pintype "bidirectional"))
    )
    (net (code "137") (name "unconnected-(H1-Pad2.40)") (class "Default")
      (node (ref "H1") (pin "2.40") (pinfunction "2.40_2.40") (pintype "bidirectional"))
    )
    (net (code "138") (name "unconnected-(H1-Pad2.41)") (class "Default")
      (node (ref "H1") (pin "2.41") (pinfunction "2.41_2.41") (pintype "bidirectional"))
    )
    (net (code "139") (name "unconnected-(H1-Pad2.42)") (class "Default")
      (node (ref "H1") (pin "2.42") (pinfunction "2.42_2.42") (pintype "bidirectional"))
    )
    (net (code "140") (name "unconnected-(H1-Pad2.43)") (class "Default")
      (node (ref "H1") (pin "2.43") (pinfunction "2.43_2.43") (pintype "bidirectional"))
    )
    (net (code "141") (name "unconnected-(H1-Pad2.44)") (class "Default")
      (node (ref "H1") (pin "2.44") (pinfunction "2.44_2.44") (pintype "bidirectional"))
    )
    (net (code "142") (name "unconnected-(H1-Pad2.45)") (class "Default")
      (node (ref "H1") (pin "2.45") (pinfunction "2.45_2.45") (pintype "bidirectional"))
    )
    (net (code "143") (name "unconnected-(H1-Pad2.46)") (class "Default")
      (node (ref "H1") (pin "2.46") (pinfunction "2.46_2.46") (pintype "bidirectional"))
    )
    (net (code "144") (name "unconnected-(H1-Pad2.49)") (class "Default")
      (node (ref "H1") (pin "2.49") (pinfunction "2.49_2.49") (pintype "bidirectional"))
    )
    (net (code "145") (name "unconnected-(H1-Pad2.50)") (class "Default")
      (node (ref "H1") (pin "2.50") (pinfunction "2.50_2.50") (pintype "bidirectional"))
    )
    (net (code "146") (name "unconnected-(H1-Pad2.51)") (class "Default")
      (node (ref "H1") (pin "2.51") (pinfunction "2.51_2.51") (pintype "bidirectional"))
    )
    (net (code "147") (name "unconnected-(H1-Pad2.52)") (class "Default")
      (node (ref "H1") (pin "2.52") (pinfunction "2.52_2.52") (pintype "bidirectional"))
    )
    (net (code "148") (name "unconnected-(H1-PadP$1)") (class "Default")
      (node (ref "H1") (pin "P$1") (pinfunction "P$1_P$1") (pintype "bidirectional"))
    )
    (net (code "149") (name "unconnected-(H1-PadP$2)") (class "Default")
      (node (ref "H1") (pin "P$2") (pinfunction "P$2_P$2") (pintype "bidirectional"))
    )
    (net (code "150") (name "unconnected-(H1-PadP$3)") (class "Default")
      (node (ref "H1") (pin "P$3") (pinfunction "P$3_P$3") (pintype "bidirectional"))
    )
    (net (code "151") (name "unconnected-(U$1-Pad30-CRX3)") (class "Default")
      (node (ref "U$1") (pin "30-CRX3") (pinfunction "30-CRX3_30-CRX3") (pintype "bidirectional"))
    )
    (net (code "152") (name "unconnected-(U$1-Pad31-CTX3)") (class "Default")
      (node (ref "U$1") (pin "31-CTX3") (pinfunction "31-CTX3_31-CTX3") (pintype "bidirectional"))
    )
    (net (code "153") (name "unconnected-(U$1-Pad32-OUT1B)") (class "Default")
      (node (ref "U$1") (pin "32-OUT1B") (pinfunction "32-OUT1B_32-OUT1B") (pintype "bidirectional"))
    )
    (net (code "154") (name "unconnected-(U$1-Pad37-PWM)") (class "Default")
      (node (ref "U$1") (pin "37-PWM") (pinfunction "37-PWM_37-PWM") (pintype "bidirectional"))
    )
    (net (code "155") (name "unconnected-(U$1-Pad40-A16{slash}CS1)") (class "Default")
      (node (ref "U$1") (pin "40-A16/CS1") (pinfunction "40-A16/CS1_40-A16/CS1") (pintype "bidirectional"))
    )
    (net (code "156") (name "unconnected-(U$1-PadON{slash}OFF)") (class "Default")
      (node (ref "U$1") (pin "ON/OFF") (pinfunction "ON/OFF_ON/OFF") (pintype "bidirectional"))
    )
    (net (code "157") (name "unconnected-(U1-NC-Pad7)") (class "Default")
      (node (ref "U1") (pin "7") (pinfunction "NC_7") (pintype "no_connect"))
    )
    (net (code "158") (name "unconnected-(U1-NC_2-Pad2)") (class "Default")
      (node (ref "U1") (pin "2") (pinfunction "NC_2_2") (pintype "no_connect"))
    )
    (net (code "159") (name "unconnected-(U1-NC_3-Pad3)") (class "Default")
      (node (ref "U1") (pin "3") (pinfunction "NC_3_3") (pintype "no_connect"))
    )
    (net (code "160") (name "unconnected-(U1-NC_4-Pad6)") (class "Default")
      (node (ref "U1") (pin "6") (pinfunction "NC_4_6") (pintype "no_connect"))
    )
    (net (code "161") (name "unconnected-(U3-GPIO_2-Pad16)") (class "Default")
      (node (ref "U3") (pin "16") (pinfunction "GPIO_2_16") (pintype "bidirectional"))
    )
    (net (code "162") (name "unconnected-(U3-NIRQ-Pad6)") (class "Default")
      (node (ref "U3") (pin "6") (pinfunction "NIRQ_6") (pintype "bidirectional"))
    )
    (net (code "163") (name "unconnected-(U3-RXON-Pad12)") (class "Default")
      (node (ref "U3") (pin "12") (pinfunction "RXON_12") (pintype "bidirectional"))
    )
    (net (code "164") (name "unconnected-(U3-SDN-Pad7)") (class "Default")
      (node (ref "U3") (pin "7") (pinfunction "SDN_7") (pintype "bidirectional"))
    )
    (net (code "165") (name "unconnected-(U3-TXON-Pad11)") (class "Default")
      (node (ref "U3") (pin "11") (pinfunction "TXON_11") (pintype "bidirectional"))
    )
    (net (code "166") (name "unconnected-(U4-DIO0-Pad14)") (class "Default")
      (node (ref "U4") (pin "14") (pinfunction "DIO0_14") (pintype "bidirectional"))
    )
    (net (code "167") (name "unconnected-(U4-DIO2-Pad16)") (class "Default")
      (node (ref "U4") (pin "16") (pinfunction "DIO2_16") (pintype "bidirectional"))
    )
    (net (code "168") (name "unconnected-(U4-DIO3-Pad11)") (class "Default")
      (node (ref "U4") (pin "11") (pinfunction "DIO3_11") (pintype "bidirectional"))
    )
    (net (code "169") (name "unconnected-(U4-DIO4-Pad12)") (class "Default")
      (node (ref "U4") (pin "12") (pinfunction "DIO4_12") (pintype "bidirectional"))
    )
    (net (code "170") (name "unconnected-(U4-DIO5-Pad7)") (class "Default")
      (node (ref "U4") (pin "7") (pinfunction "DIO5_7") (pintype "bidirectional"))
    )
    (net (code "171") (name "unconnected-(U5-Pad1)") (class "Default")
      (node (ref "U5") (pin "1") (pinfunction "1_1") (pintype "passive"))
    )
    (net (code "172") (name "unconnected-(U6-P$3-Pad3)") (class "Default")
      (node (ref "U6") (pin "3") (pinfunction "P$3_3") (pintype "bidirectional"))
    )
    (net (code "173") (name "unconnected-(U6-P$4-Pad4)") (class "Default")
      (node (ref "U6") (pin "4") (pinfunction "P$4_4") (pintype "bidirectional"))
    )
    (net (code "174") (name "unconnected-(U6-P$5-Pad5)") (class "Default")
      (node (ref "U6") (pin "5") (pinfunction "P$5_5") (pintype "bidirectional"))
    )
    (net (code "175") (name "unconnected-(U6-P$6-Pad6)") (class "Default")
      (node (ref "U6") (pin "6") (pinfunction "P$6_6") (pintype "bidirectional"))
    )
    (net (code "176") (name "unconnected-(U6-P$8-Pad8)") (class "Default")
      (node (ref "U6") (pin "8") (pinfunction "P$8_8") (pintype "bidirectional"))
    )
    (net (code "177") (name "unconnected-(U6-P$12-Pad12)") (class "Default")
      (node (ref "U6") (pin "12") (pinfunction "P$12_12") (pintype "bidirectional"))
    )
    (net (code "178") (name "unconnected-(U6-P$13-Pad13)") (class "Default")
      (node (ref "U6") (pin "13") (pinfunction "P$13_13") (pintype "bidirectional"))
    )
    (net (code "179") (name "unconnected-(U6-P$14-Pad14)") (class "Default")
      (node (ref "U6") (pin "14") (pinfunction "P$14_14") (pintype "bidirectional"))
    )
    (net (code "180") (name "unconnected-(U6-P$16-Pad16)") (class "Default")
      (node (ref "U6") (pin "16") (pinfunction "P$16_16") (pintype "bidirectional"))
    )
    (net (code "181") (name "unconnected-(U6-P$17-Pad17)") (class "Default")
      (node (ref "U6") (pin "17") (pinfunction "P$17_17") (pintype "bidirectional"))
    )
    (net (code "182") (name "unconnected-(U6-P$20-Pad20)") (class "Default")
      (node (ref "U6") (pin "20") (pinfunction "P$20_20") (pintype "bidirectional"))
    )
    (net (code "183") (name "unconnected-(U6-P$23-Pad23)") (class "Default")
      (node (ref "U6") (pin "23") (pinfunction "P$23_23") (pintype "bidirectional"))
    )
    (net (code "184") (name "unconnected-(U6-P$26-Pad26)") (class "Default")
      (node (ref "U6") (pin "26") (pinfunction "P$26_26") (pintype "bidirectional"))
    )
    (net (code "185") (name "unconnected-(U6-P$30-Pad30)") (class "Default")
      (node (ref "U6") (pin "30") (pinfunction "P$30_30") (pintype "bidirectional"))
    )
    (net (code "186") (name "unconnected-(U6-P$34-Pad34)") (class "Default")
      (node (ref "U6") (pin "34") (pinfunction "P$34_34") (pintype "bidirectional"))
    )
    (net (code "187") (name "unconnected-(U6-P$35-Pad35)") (class "Default")
      (node (ref "U6") (pin "35") (pinfunction "P$35_35") (pintype "bidirectional"))
    )
    (net (code "188") (name "unconnected-(U6-P$36-Pad36)") (class "Default")
      (node (ref "U6") (pin "36") (pinfunction "P$36_36") (pintype "bidirectional"))
    )
    (net (code "189") (name "unconnected-(U6-P$37-Pad37)") (class "Default")
      (node (ref "U6") (pin "37") (pinfunction "P$37_37") (pintype "bidirectional"))
    )
    (net (code "190") (name "unconnected-(U6-P$38-Pad38)") (class "Default")
      (node (ref "U6") (pin "38") (pinfunction "P$38_38") (pintype "bidirectional"))
    )
    (net (code "191") (name "unconnected-(U6-P$39-Pad39)") (class "Default")
      (node (ref "U6") (pin "39") (pinfunction "P$39_39") (pintype "bidirectional"))
    )
    (net (code "192") (name "unconnected-(U6-P$40-Pad40)") (class "Default")
      (node (ref "U6") (pin "40") (pinfunction "P$40_40") (pintype "bidirectional"))
    )
    (net (code "193") (name "unconnected-(U6-P$41-Pad41)") (class "Default")
      (node (ref "U6") (pin "41") (pinfunction "P$41_41") (pintype "bidirectional"))
    )
    (net (code "194") (name "unconnected-(U6-P$43-Pad43)") (class "Default")
      (node (ref "U6") (pin "43") (pinfunction "P$43_43") (pintype "bidirectional"))
    )
    (net (code "195") (name "unconnected-(U6-P$45-Pad45)") (class "Default")
      (node (ref "U6") (pin "45") (pinfunction "P$45_45") (pintype "bidirectional"))
    )
    (net (code "196") (name "unconnected-(U6-P$46-Pad46)") (class "Default")
      (node (ref "U6") (pin "46") (pinfunction "P$46_46") (pintype "bidirectional"))
    )
    (net (code "197") (name "unconnected-(U6-P$47-Pad47)") (class "Default")
      (node (ref "U6") (pin "47") (pinfunction "P$47_47") (pintype "bidirectional"))
    )
    (net (code "198") (name "unconnected-(U6-P$48-Pad48)") (class "Default")
      (node (ref "U6") (pin "48") (pinfunction "P$48_48") (pintype "bidirectional"))
    )
    (net (code "199") (name "unconnected-(U6-P$49-Pad49)") (class "Default")
      (node (ref "U6") (pin "49") (pinfunction "P$49_49") (pintype "bidirectional"))
    )
    (net (code "200") (name "unconnected-(U6-P$50-Pad50)") (class "Default")
      (node (ref "U6") (pin "50") (pinfunction "P$50_50") (pintype "bidirectional"))
    )
    (net (code "201") (name "unconnected-(U6-P$51-Pad51)") (class "Default")
      (node (ref "U6") (pin "51") (pinfunction "P$51_51") (pintype "bidirectional"))
    )
    (net (code "202") (name "unconnected-(U6-P$52-Pad52)") (class "Default")
      (node (ref "U6") (pin "52") (pinfunction "P$52_52") (pintype "bidirectional"))
    )
    (net (code "203") (name "unconnected-(U6-P$53-Pad53)") (class "Default")
      (node (ref "U6") (pin "53") (pinfunction "P$53_53") (pintype "bidirectional"))
    )
    (net (code "204") (name "unconnected-(U6-P$54-Pad54)") (class "Default")
      (node (ref "U6") (pin "54") (pinfunction "P$54_54") (pintype "bidirectional"))
    )
    (net (code "205") (name "unconnected-(U6-P$55-Pad55)") (class "Default")
      (node (ref "U6") (pin "55") (pinfunction "P$55_55") (pintype "bidirectional"))
    )
    (net (code "206") (name "unconnected-(U6-P$56-Pad56)") (class "Default")
      (node (ref "U6") (pin "56") (pinfunction "P$56_56") (pintype "bidirectional"))
    )
    (net (code "207") (name "unconnected-(U6-P$57-Pad57)") (class "Default")
      (node (ref "U6") (pin "57") (pinfunction "P$57_57") (pintype "bidirectional"))
    )
    (net (code "208") (name "unconnected-(U6-P$59-Pad59)") (class "Default")
      (node (ref "U6") (pin "59") (pinfunction "P$59_59") (pintype "bidirectional"))
    )
    (net (code "209") (name "unconnected-(U6-P$60-Pad60)") (class "Default")
      (node (ref "U6") (pin "60") (pinfunction "P$60_60") (pintype "bidirectional"))
    )
    (net (code "210") (name "unconnected-(U6-P$61-Pad61)") (class "Default")
      (node (ref "U6") (pin "61") (pinfunction "P$61_61") (pintype "bidirectional"))
    )
    (net (code "211") (name "unconnected-(U6-P$62-Pad62)") (class "Default")
      (node (ref "U6") (pin "62") (pinfunction "P$62_62") (pintype "bidirectional"))
    )
    (net (code "212") (name "unconnected-(U6-P$63-Pad63)") (class "Default")
      (node (ref "U6") (pin "63") (pinfunction "P$63_63") (pintype "bidirectional"))
    )
    (net (code "213") (name "unconnected-(U6-P$65-Pad65)") (class "Default")
      (node (ref "U6") (pin "65") (pinfunction "P$65_65") (pintype "bidirectional"))
    )
    (net (code "214") (name "unconnected-(U6-P$66-Pad66)") (class "Default")
      (node (ref "U6") (pin "66") (pinfunction "P$66_66") (pintype "bidirectional"))
    )
    (net (code "215") (name "unconnected-(U6-P$67-Pad67)") (class "Default")
      (node (ref "U6") (pin "67") (pinfunction "P$67_67") (pintype "bidirectional"))
    )
    (net (code "216") (name "unconnected-(U6-P$68-Pad68)") (class "Default")
      (node (ref "U6") (pin "68") (pinfunction "P$68_68") (pintype "bidirectional"))
    )
    (net (code "217") (name "unconnected-(U6-P$69-Pad69)") (class "Default")
      (node (ref "U6") (pin "69") (pinfunction "P$69_69") (pintype "bidirectional"))
    )
    (net (code "218") (name "unconnected-(X1-P$1-Pad1)") (class "Default")
      (node (ref "X1") (pin "1") (pinfunction "P$1_1") (pintype "bidirectional"))
    )
    (net (code "219") (name "unconnected-(X1-P$4-Pad4)") (class "Default")
      (node (ref "X1") (pin "4") (pinfunction "P$4_4") (pintype "bidirectional"))
    )
    (net (code "220") (name "unconnected-(X1-P$6-Pad6)") (class "Default")
      (node (ref "X1") (pin "6") (pinfunction "P$6_6") (pintype "bidirectional"))
    )
    (net (code "221") (name "unconnected-(X1-P$7-Pad7)") (class "Default")
      (node (ref "X1") (pin "7") (pinfunction "P$7_7") (pintype "bidirectional"))
    )
    (net (code "222") (name "unconnected-(X1-P$8-Pad8)") (class "Default")
      (node (ref "X1") (pin "8") (pinfunction "P$8_8") (pintype "bidirectional"))
    )
    (net (code "223") (name "unconnected-(X1-P$9-Pad9)") (class "Default")
      (node (ref "X1") (pin "9") (pinfunction "P$9_9") (pintype "bidirectional"))
    )
    (net (code "224") (name "unconnected-(X1-P$10-Pad10)") (class "Default")
      (node (ref "X1") (pin "10") (pinfunction "P$10_10") (pintype "bidirectional"))
    )
    (net (code "225") (name "unconnected-(X1-P$12-Pad12)") (class "Default")
      (node (ref "X1") (pin "12") (pinfunction "P$12_12") (pintype "bidirectional"))
    )
    (net (code "226") (name "unconnected-(X1-P$14-Pad14)") (class "Default")
      (node (ref "X1") (pin "14") (pinfunction "P$14_14") (pintype "bidirectional"))
    )
    (net (code "227") (name "unconnected-(X1-P$17-Pad17)") (class "Default")
      (node (ref "X1") (pin "17") (pinfunction "P$17_17") (pintype "bidirectional"))
    )
    (net (code "228") (name "unconnected-(X1-P$20-Pad20)") (class "Default")
      (node (ref "X1") (pin "20") (pinfunction "P$20_20") (pintype "bidirectional"))
    )
    (net (code "229") (name "unconnected-(X1-P$25-Pad25)") (class "Default")
      (node (ref "X1") (pin "25") (pinfunction "P$25_25") (pintype "bidirectional"))
    )
    (net (code "230") (name "unconnected-(X1-P$27-Pad27)") (class "Default")
      (node (ref "X1") (pin "27") (pinfunction "P$27_27") (pintype "bidirectional"))
    )
    (net (code "231") (name "unconnected-(X1-P$28-Pad28)") (class "Default")
      (node (ref "X1") (pin "28") (pinfunction "P$28_28") (pintype "bidirectional"))
    )
    (net (code "232") (name "unconnected-(X1-P$29-Pad29)") (class "Default")
      (node (ref "X1") (pin "29") (pinfunction "P$29_29") (pintype "bidirectional"))
    )
    (net (code "233") (name "unconnected-(X1-P$30-Pad30)") (class "Default")
      (node (ref "X1") (pin "30") (pinfunction "P$30_30") (pintype "bidirectional"))
    )
    (net (code "234") (name "unconnected-(X1-P$31-Pad31)") (class "Default")
      (node (ref "X1") (pin "31") (pinfunction "P$31_31") (pintype "bidirectional"))
    )
    (net (code "235") (name "unconnected-(X1-P$32-Pad32)") (class "Default")
      (node (ref "X1") (pin "32") (pinfunction "P$32_32") (pintype "bidirectional"))
    )
    (net (code "236") (name "unconnected-(X1-P$33-Pad33)") (class "Default")
      (node (ref "X1") (pin "33") (pinfunction "P$33_33") (pintype "bidirectional"))
    )
    (net (code "237") (name "unconnected-(X1-P$34-Pad34)") (class "Default")
      (node (ref "X1") (pin "34") (pinfunction "P$34_34") (pintype "bidirectional"))
    )
    (net (code "238") (name "unconnected-(X1-P$35-Pad35)") (class "Default")
      (node (ref "X1") (pin "35") (pinfunction "P$35_35") (pintype "bidirectional"))
    )
    (net (code "239") (name "unconnected-(X1-P$36-Pad36)") (class "Default")
      (node (ref "X1") (pin "36") (pinfunction "P$36_36") (pintype "bidirectional"))
    )
    (net (code "240") (name "unconnected-(X1-P$37-Pad37)") (class "Default")
      (node (ref "X1") (pin "37") (pinfunction "P$37_37") (pintype "bidirectional"))
    )
    (net (code "241") (name "unconnected-(X1-P$38-Pad38)") (class "Default")
      (node (ref "X1") (pin "38") (pinfunction "P$38_38") (pintype "bidirectional"))
    )
    (net (code "242") (name "unconnected-(X1-P$40-Pad40)") (class "Default")
      (node (ref "X1") (pin "40") (pinfunction "P$40_40") (pintype "bidirectional"))
    )
    (net (code "243") (name "unconnected-(X2-Pad1)") (class "Default")
      (node (ref "X2") (pin "1") (pinfunction "1_1") (pintype "passive"))
    )
    (net (code "244") (name "unconnected-(X2AA-1-Pad33)") (class "Default")
      (node (ref "X2") (pin "33") (pinfunction "1_33") (pintype "passive"))
    )
    (net (code "245") (name "unconnected-(X2AB-1-Pad34)") (class "Default")
      (node (ref "X2") (pin "34") (pinfunction "1_34") (pintype "passive"))
    )
    (net (code "246") (name "unconnected-(X2AC-1-Pad35)") (class "Default")
      (node (ref "X2") (pin "35") (pinfunction "1_35") (pintype "passive"))
    )
    (net (code "247") (name "unconnected-(X2AD-1-Pad36)") (class "Default")
      (node (ref "X2") (pin "36") (pinfunction "1_36") (pintype "passive"))
    )
    (net (code "248") (name "unconnected-(X2AE-1-Pad37)") (class "Default")
      (node (ref "X2") (pin "37") (pinfunction "1_37") (pintype "passive"))
    )
    (net (code "249") (name "unconnected-(X2AF-1-Pad38)") (class "Default")
      (node (ref "X2") (pin "38") (pinfunction "1_38") (pintype "passive"))
    )
    (net (code "250") (name "unconnected-(X2AG-1-Pad39)") (class "Default")
      (node (ref "X2") (pin "39") (pinfunction "1_39") (pintype "passive"))
    )
    (net (code "251") (name "unconnected-(X2AH-1-Pad4)") (class "Default")
      (node (ref "X2") (pin "4") (pinfunction "1_4") (pintype "passive"))
    )
    (net (code "252") (name "unconnected-(X2AI-1-Pad40)") (class "Default")
      (node (ref "X2") (pin "40") (pinfunction "1_40") (pintype "passive"))
    )
    (net (code "253") (name "unconnected-(X2AJ-1-Pad5)") (class "Default")
      (node (ref "X2") (pin "5") (pinfunction "1_5") (pintype "passive"))
    )
    (net (code "254") (name "unconnected-(X2AK-1-Pad6)") (class "Default")
      (node (ref "X2") (pin "6") (pinfunction "1_6") (pintype "passive"))
    )
    (net (code "255") (name "unconnected-(X2AL-1-Pad7)") (class "Default")
      (node (ref "X2") (pin "7") (pinfunction "1_7") (pintype "passive"))
    )
    (net (code "256") (name "unconnected-(X2AM-1-Pad8)") (class "Default")
      (node (ref "X2") (pin "8") (pinfunction "1_8") (pintype "passive"))
    )
    (net (code "257") (name "unconnected-(X2AN-1-Pad9)") (class "Default")
      (node (ref "X2") (pin "9") (pinfunction "1_9") (pintype "passive"))
    )
    (net (code "258") (name "unconnected-(X2B-1-Pad10)") (class "Default")
      (node (ref "X2") (pin "10") (pinfunction "1_10") (pintype "passive"))
    )
    (net (code "259") (name "unconnected-(X2C-1-Pad11)") (class "Default")
      (node (ref "X2") (pin "11") (pinfunction "1_11") (pintype "passive"))
    )
    (net (code "260") (name "unconnected-(X2D-1-Pad12)") (class "Default")
      (node (ref "X2") (pin "12") (pinfunction "1_12") (pintype "passive"))
    )
    (net (code "261") (name "unconnected-(X2E-1-Pad13)") (class "Default")
      (node (ref "X2") (pin "13") (pinfunction "1_13") (pintype "passive"))
    )
    (net (code "262") (name "unconnected-(X2F-1-Pad14)") (class "Default")
      (node (ref "X2") (pin "14") (pinfunction "1_14") (pintype "passive"))
    )
    (net (code "263") (name "unconnected-(X2G-1-Pad15)") (class "Default")
      (node (ref "X2") (pin "15") (pinfunction "1_15") (pintype "passive"))
    )
    (net (code "264") (name "unconnected-(X2H-1-Pad16)") (class "Default")
      (node (ref "X2") (pin "16") (pinfunction "1_16") (pintype "passive"))
    )
    (net (code "265") (name "unconnected-(X2I-1-Pad17)") (class "Default")
      (node (ref "X2") (pin "17") (pinfunction "1_17") (pintype "passive"))
    )
    (net (code "266") (name "unconnected-(X2J-1-Pad18)") (class "Default")
      (node (ref "X2") (pin "18") (pinfunction "1_18") (pintype "passive"))
    )
    (net (code "267") (name "unconnected-(X2K-1-Pad19)") (class "Default")
      (node (ref "X2") (pin "19") (pinfunction "1_19") (pintype "passive"))
    )
    (net (code "268") (name "unconnected-(X2L-1-Pad2)") (class "Default")
      (node (ref "X2") (pin "2") (pinfunction "1_2") (pintype "passive"))
    )
    (net (code "269") (name "unconnected-(X2M-1-Pad20)") (class "Default")
      (node (ref "X2") (pin "20") (pinfunction "1_20") (pintype "passive"))
    )
    (net (code "270") (name "unconnected-(X2N-1-Pad21)") (class "Default")
      (node (ref "X2") (pin "21") (pinfunction "1_21") (pintype "passive"))
    )
    (net (code "271") (name "unconnected-(X2O-1-Pad22)") (class "Default")
      (node (ref "X2") (pin "22") (pinfunction "1_22") (pintype "passive"))
    )
    (net (code "272") (name "unconnected-(X2P-1-Pad23)") (class "Default")
      (node (ref "X2") (pin "23") (pinfunction "1_23") (pintype "passive"))
    )
    (net (code "273") (name "unconnected-(X2Q-1-Pad24)") (class "Default")
      (node (ref "X2") (pin "24") (pinfunction "1_24") (pintype "passive"))
    )
    (net (code "274") (name "unconnected-(X2R-1-Pad25)") (class "Default")
      (node (ref "X2") (pin "25") (pinfunction "1_25") (pintype "passive"))
    )
    (net (code "275") (name "unconnected-(X2S-1-Pad26)") (class "Default")
      (node (ref "X2") (pin "26") (pinfunction "1_26") (pintype "passive"))
    )
    (net (code "276") (name "unconnected-(X2T-1-Pad27)") (class "Default")
      (node (ref "X2") (pin "27") (pinfunction "1_27") (pintype "passive"))
    )
    (net (code "277") (name "unconnected-(X2U-1-Pad28)") (class "Default")
      (node (ref "X2") (pin "28") (pinfunction "1_28") (pintype "passive"))
    )
    (net (code "278") (name "unconnected-(X2V-1-Pad29)") (class "Default")
      (node (ref "X2") (pin "29") (pinfunction "1_29") (pintype "passive"))
    )
    (net (code "279") (name "unconnected-(X2W-1-Pad3)") (class "Default")
      (node (ref "X2") (pin "3") (pinfunction "1_3") (pintype "passive"))
    )
    (net (code "280") (name "unconnected-(X2X-1-Pad30)") (class "Default")
      (node (ref "X2") (pin "30") (pinfunction "1_30") (pintype "passive"))
    )
    (net (code "281") (name "unconnected-(X2Y-1-Pad31)") (class "Default")
      (node (ref "X2") (pin "31") (pinfunction "1_31") (pintype "passive"))
    )
    (net (code "282") (name "unconnected-(X2Z-1-Pad32)") (class "Default")
      (node (ref "X2") (pin "32") (pinfunction "1_32") (pintype "passive"))
    )
  )
)
